# AnalogConversion_v3.net
KiCad netlist of a schematic drawn in EAGLE
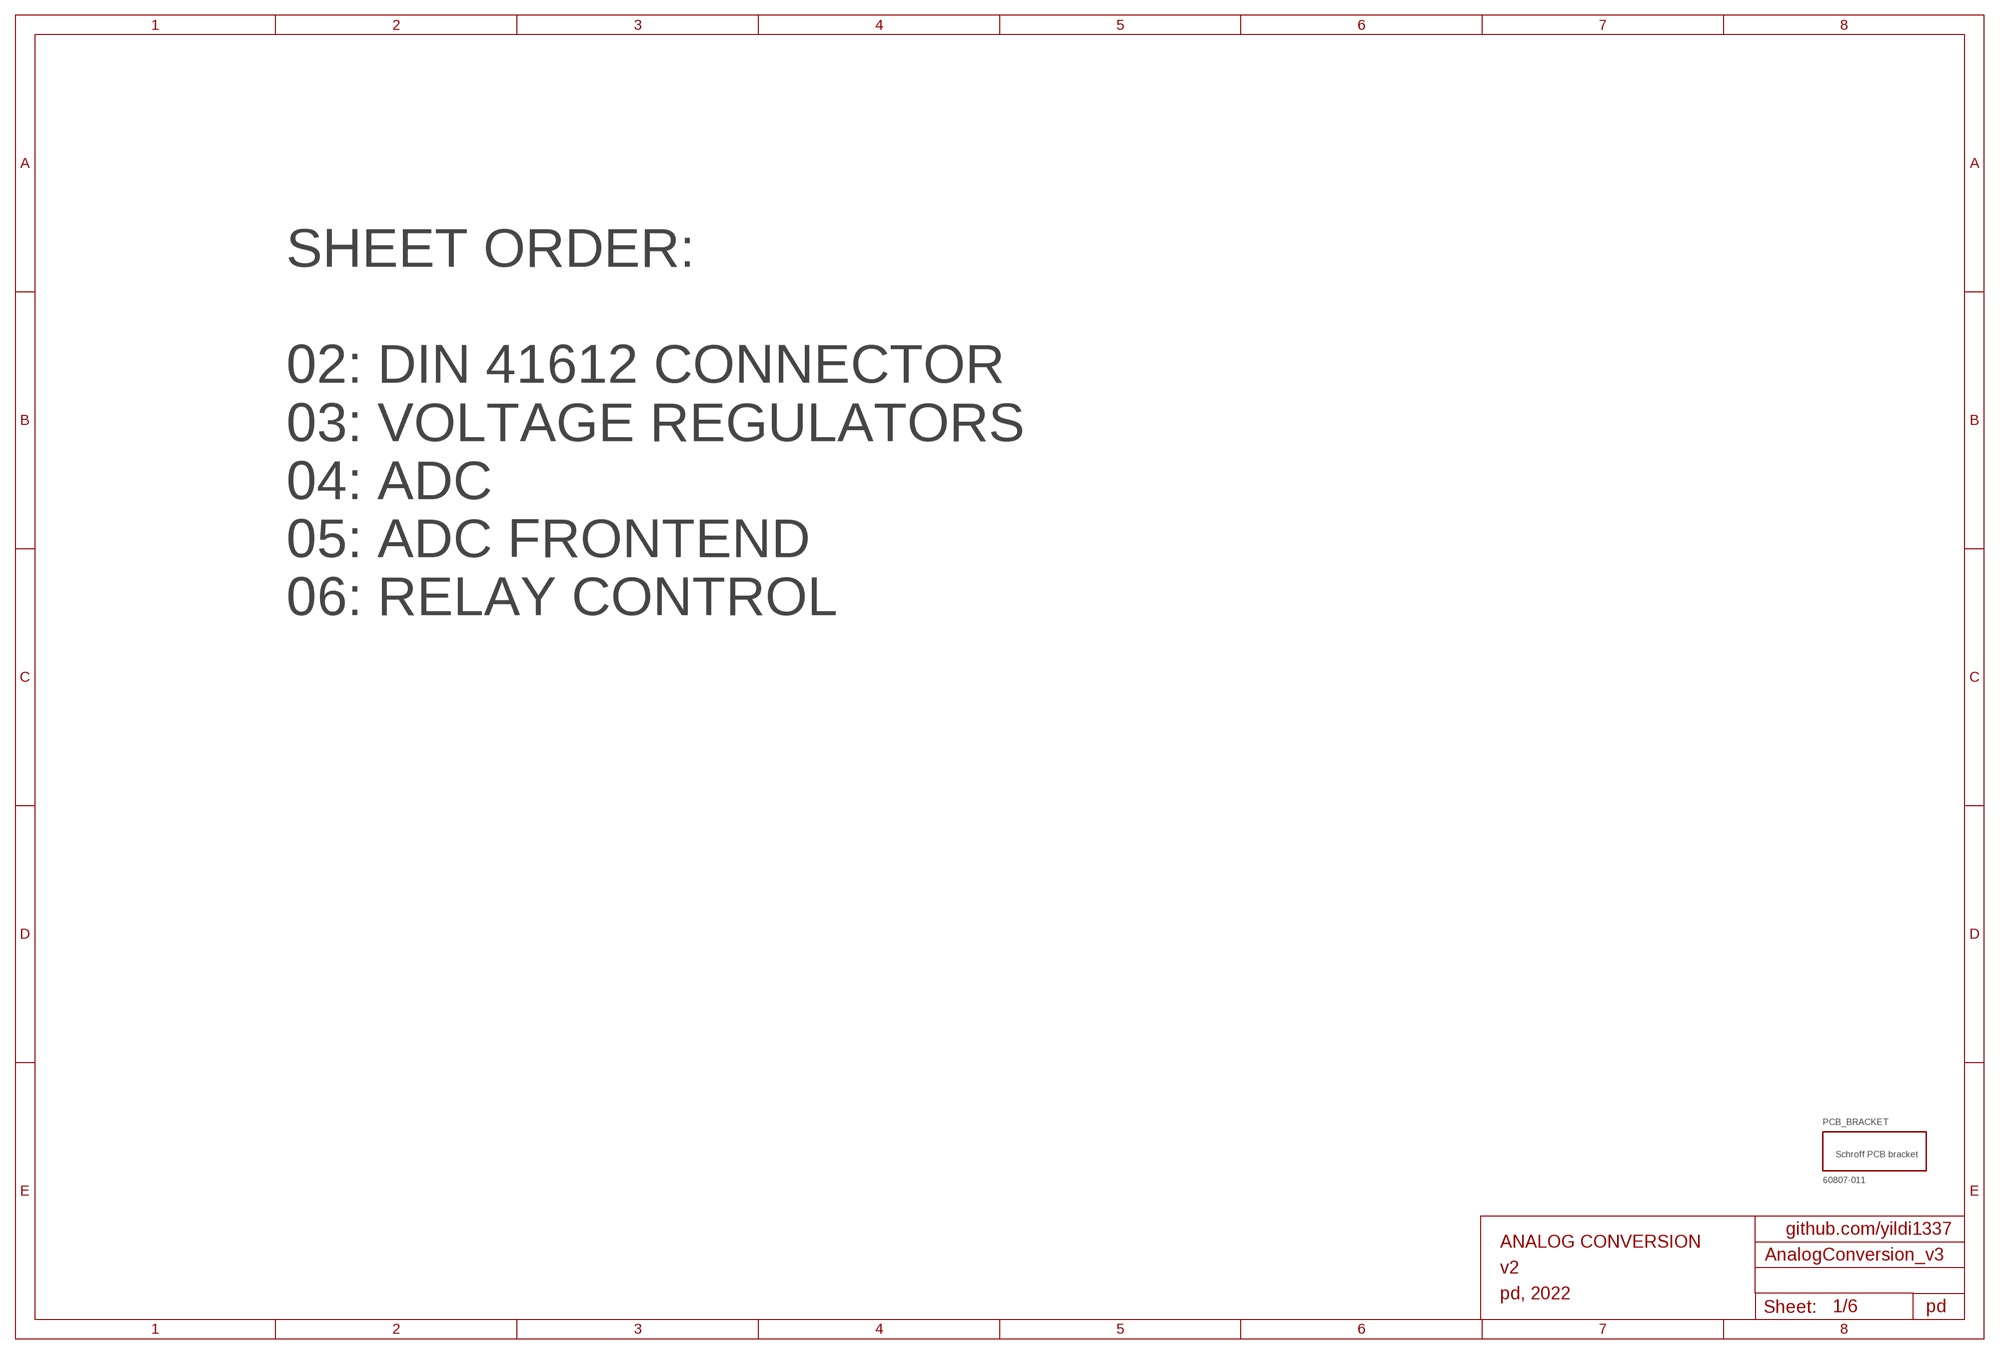
[diagram p0: schematic, sheet 1]
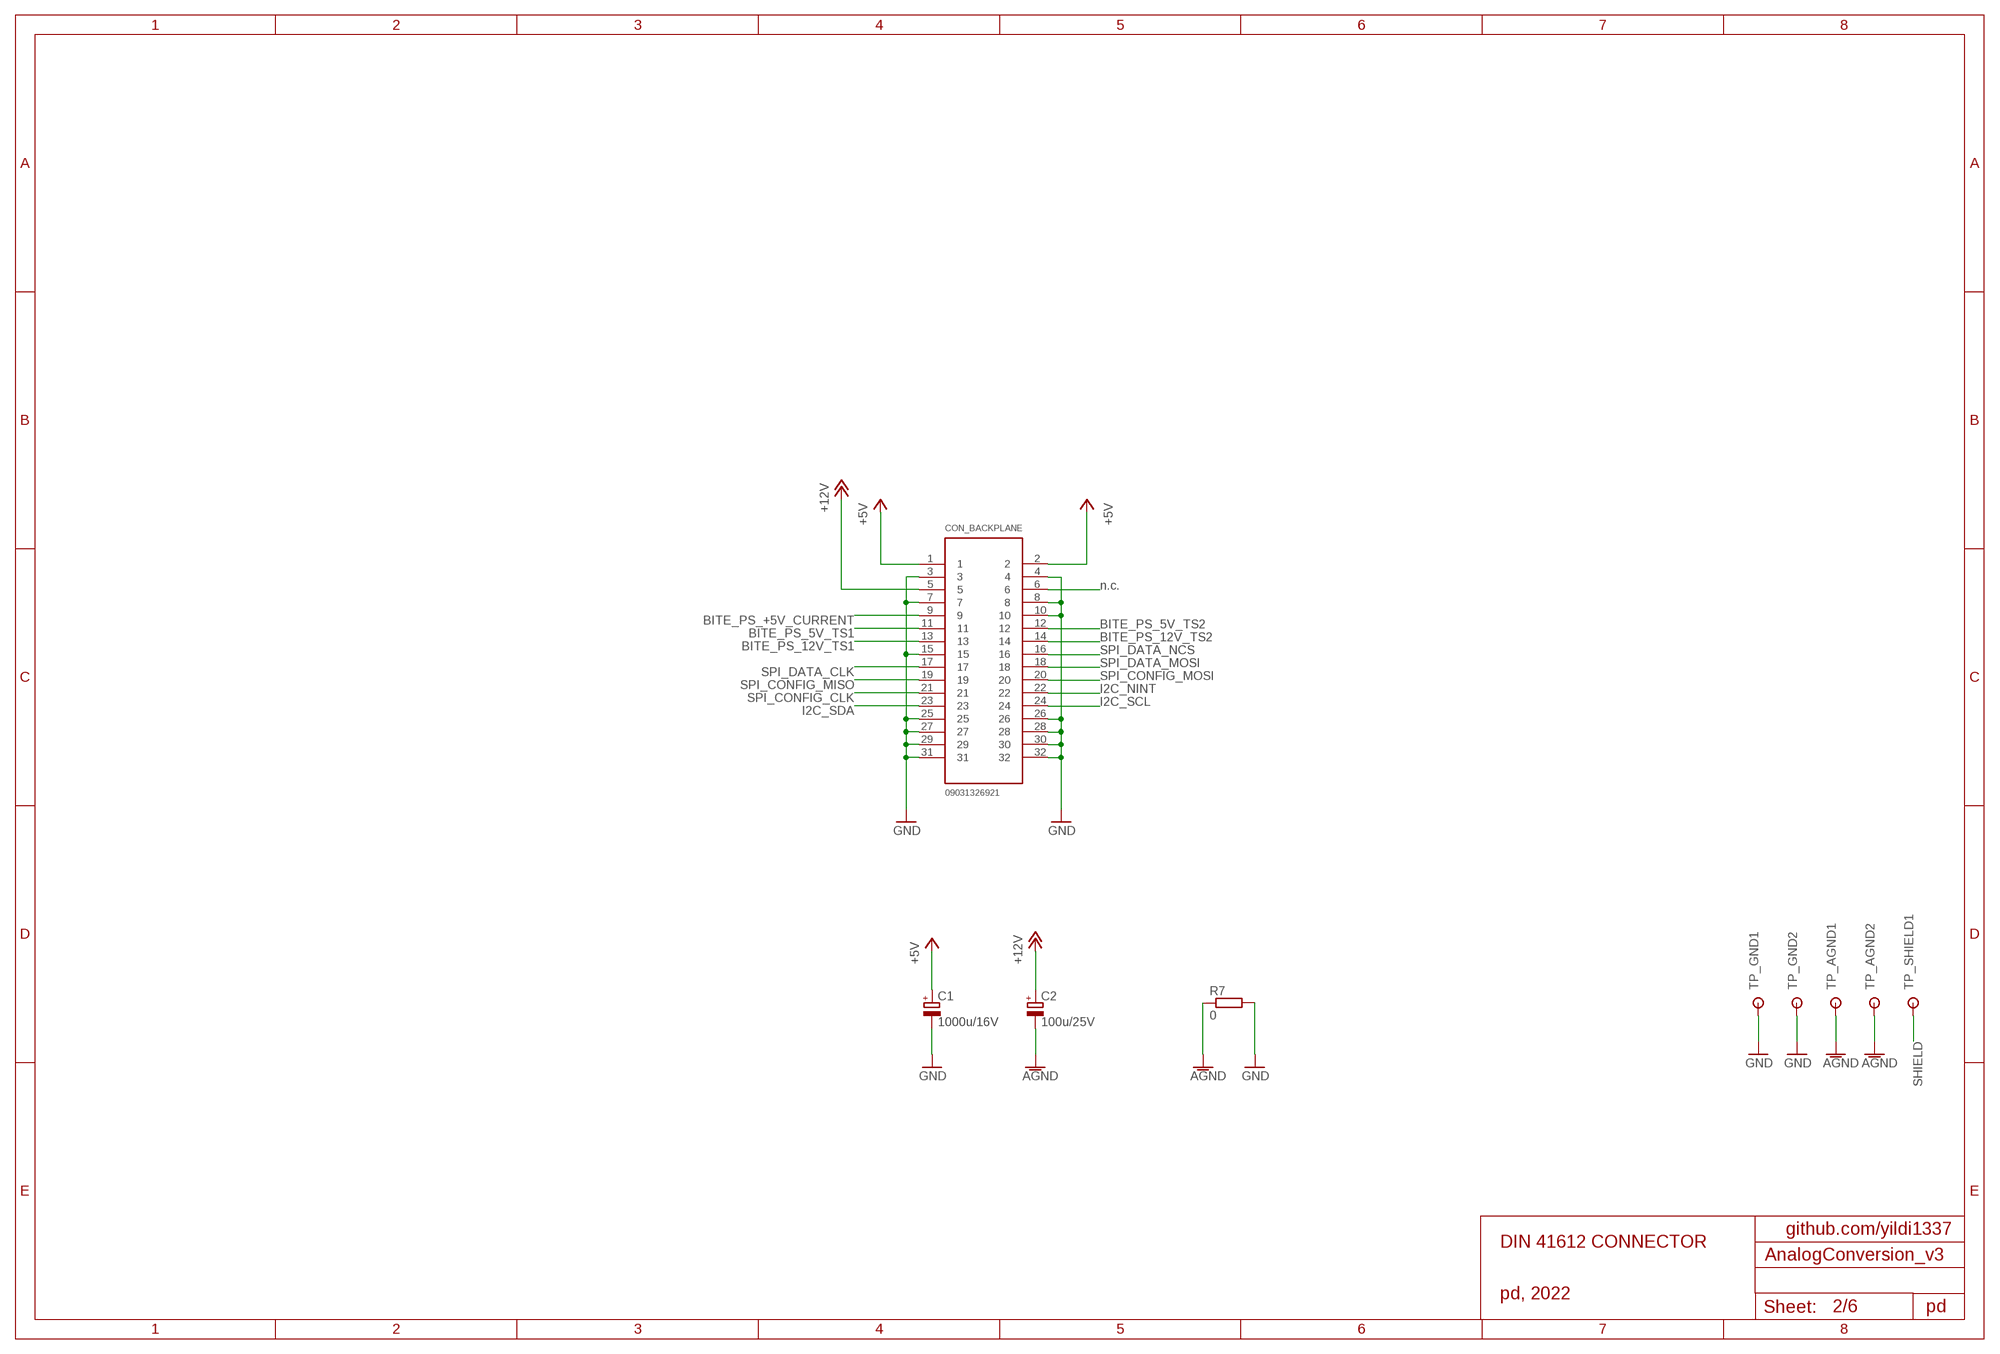
[diagram p1: schematic, sheet 2]
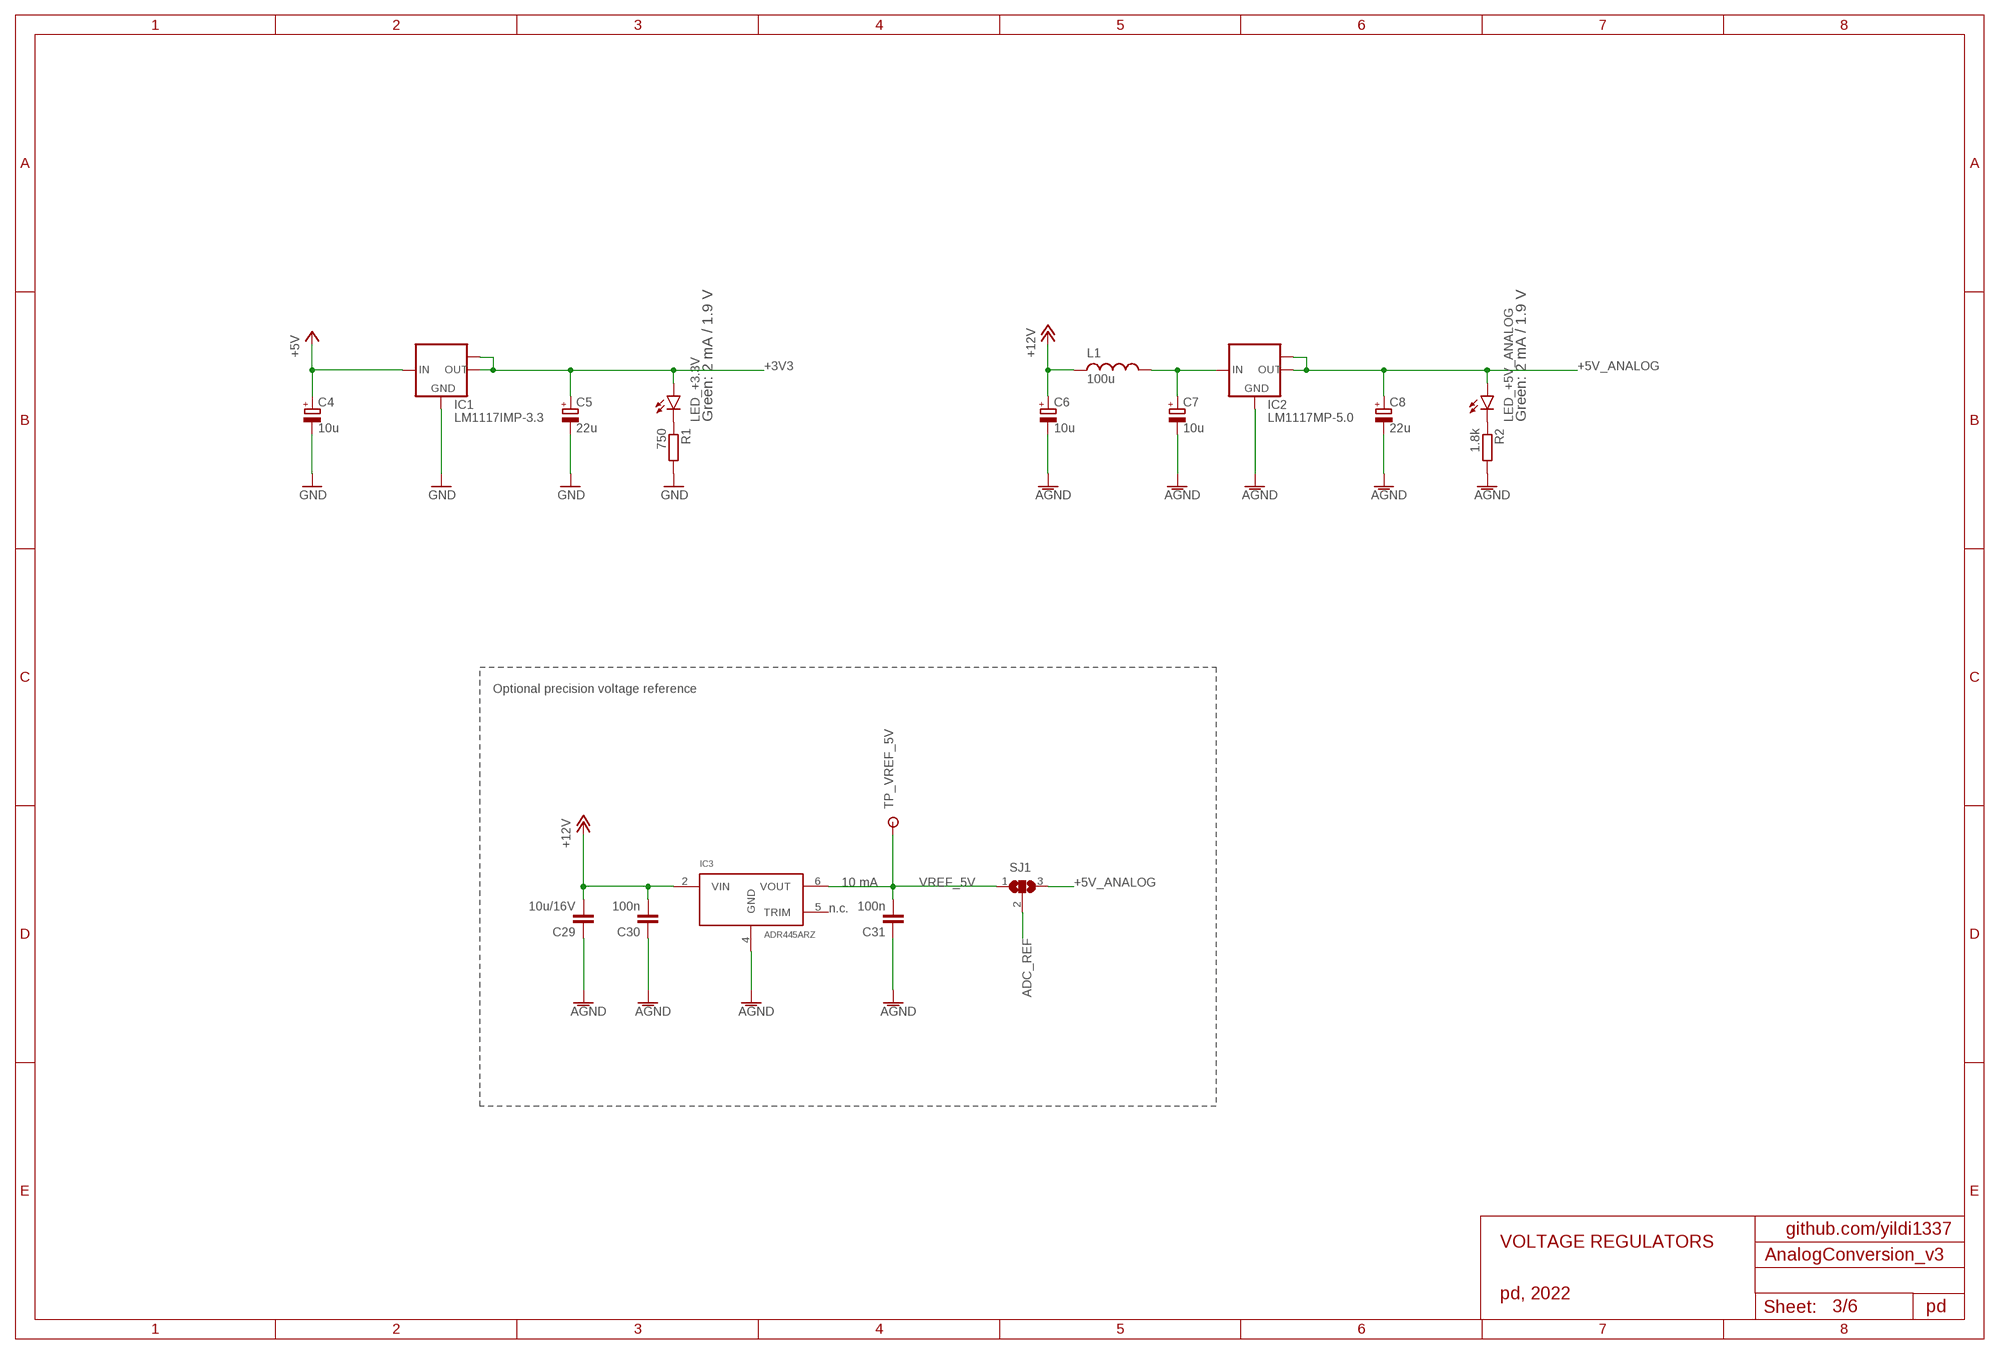
[diagram p2: schematic, sheet 3]
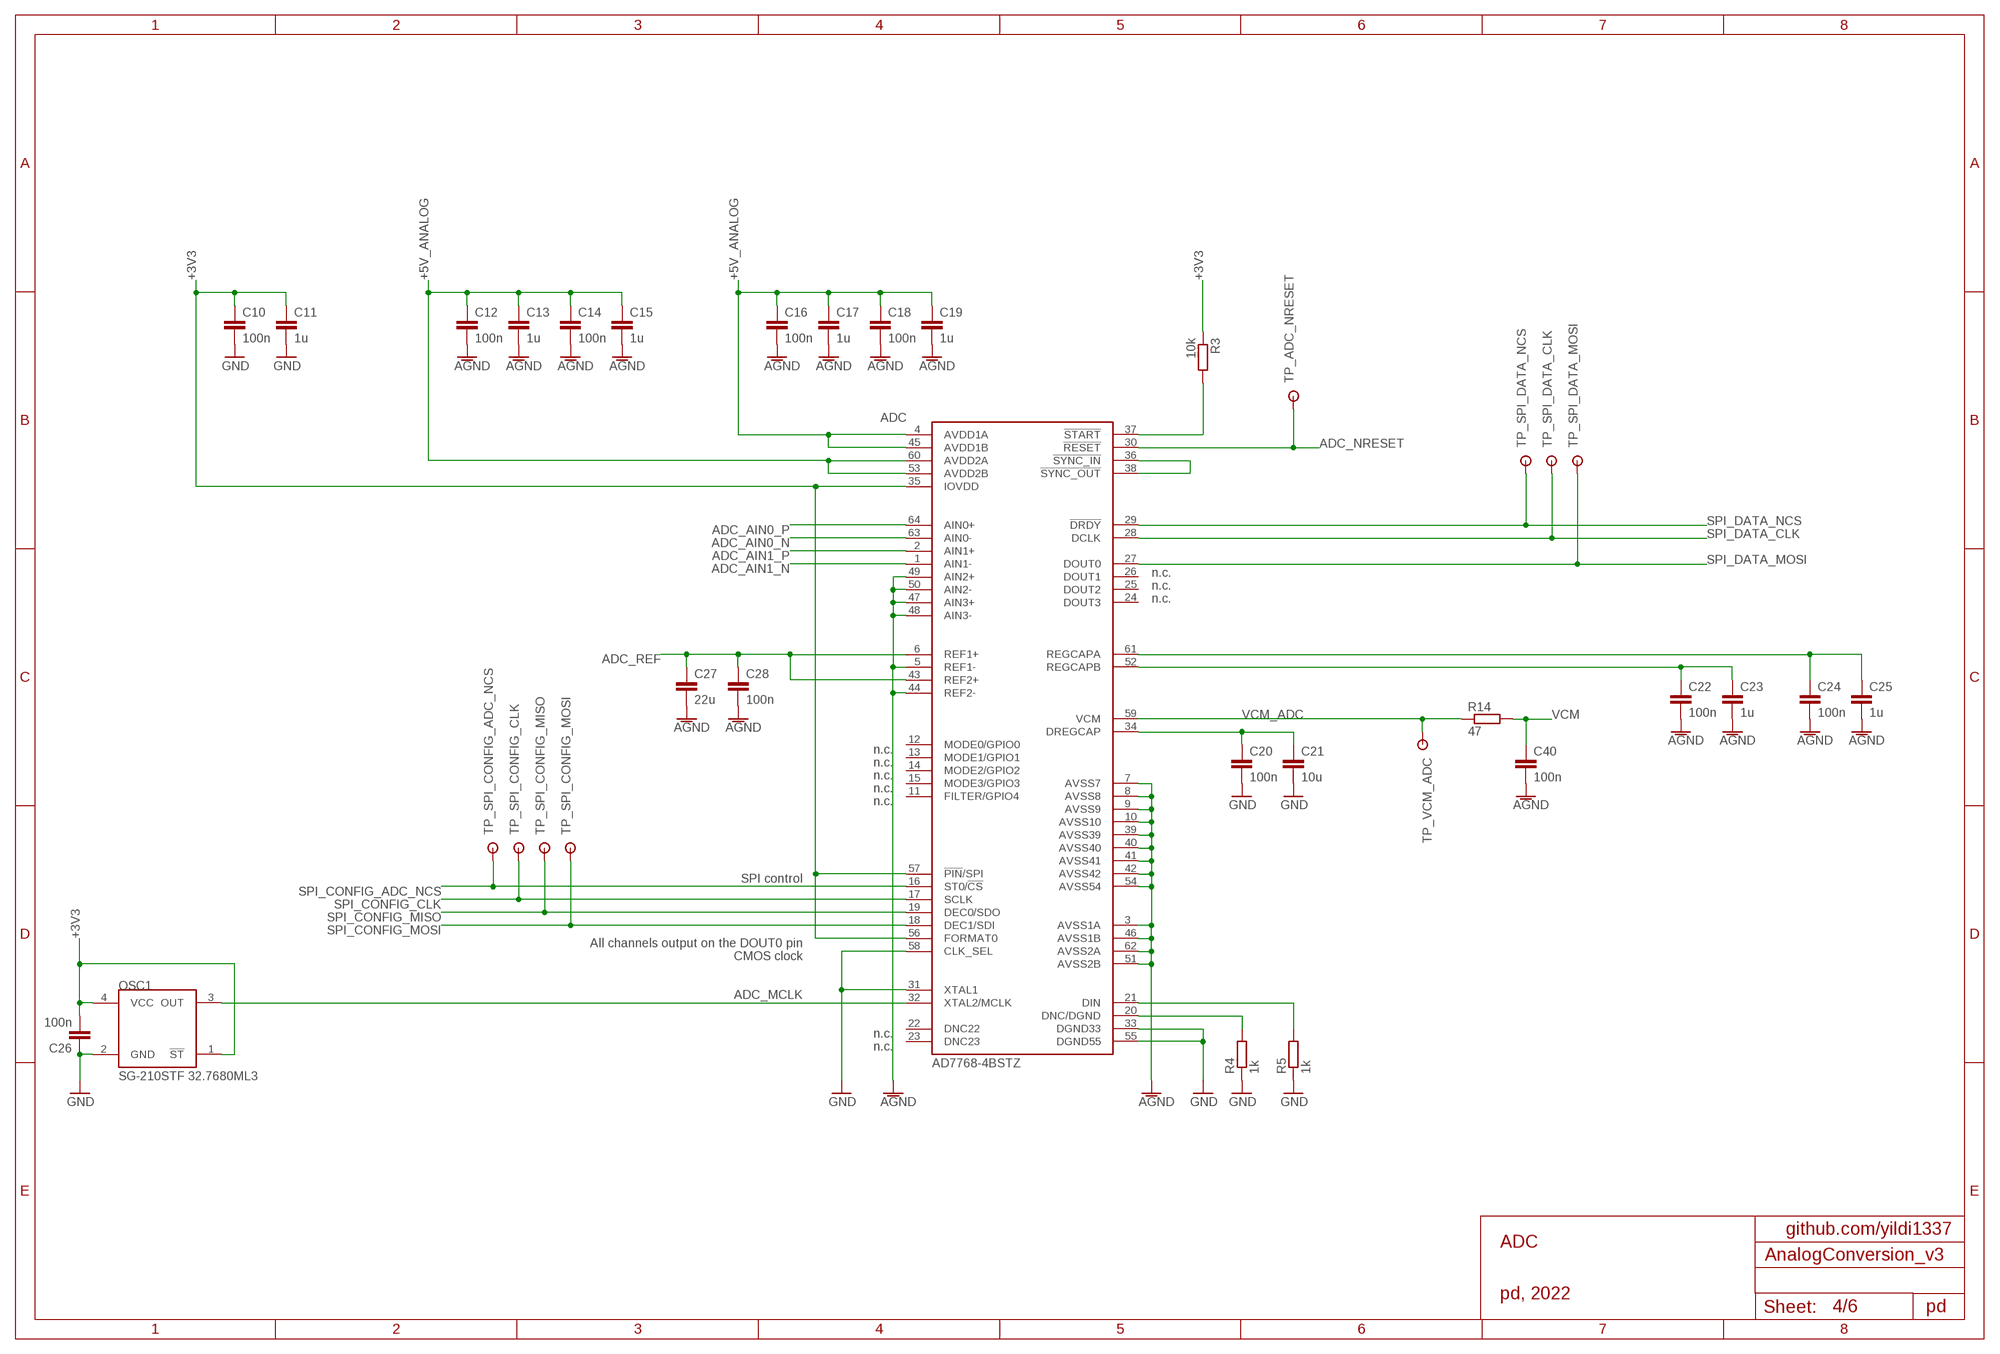
[diagram p3: schematic, sheet 4]
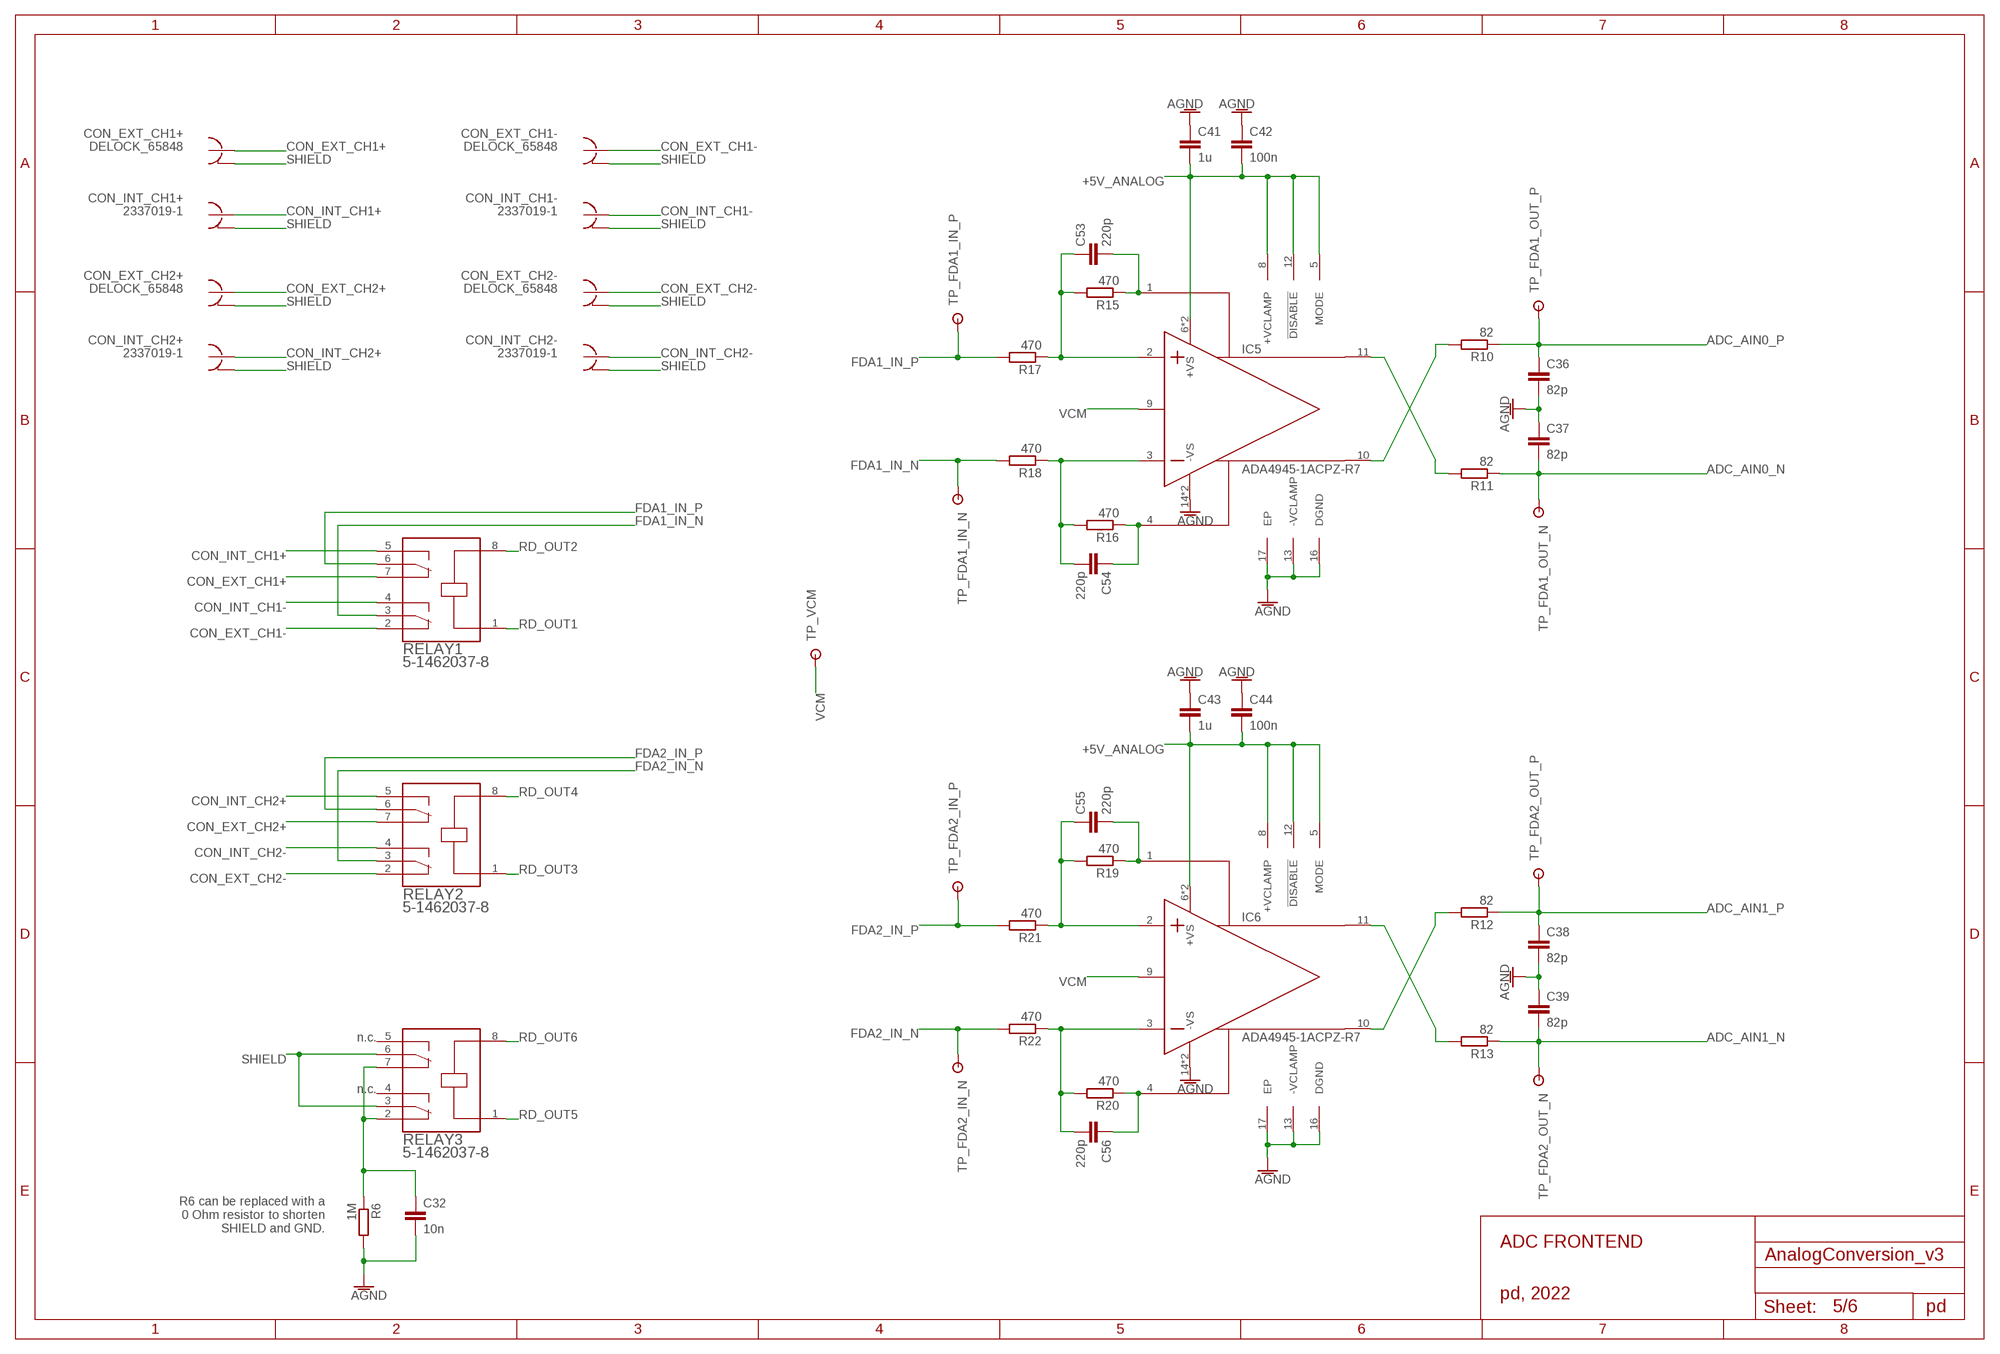
[diagram p4: schematic, sheet 5]
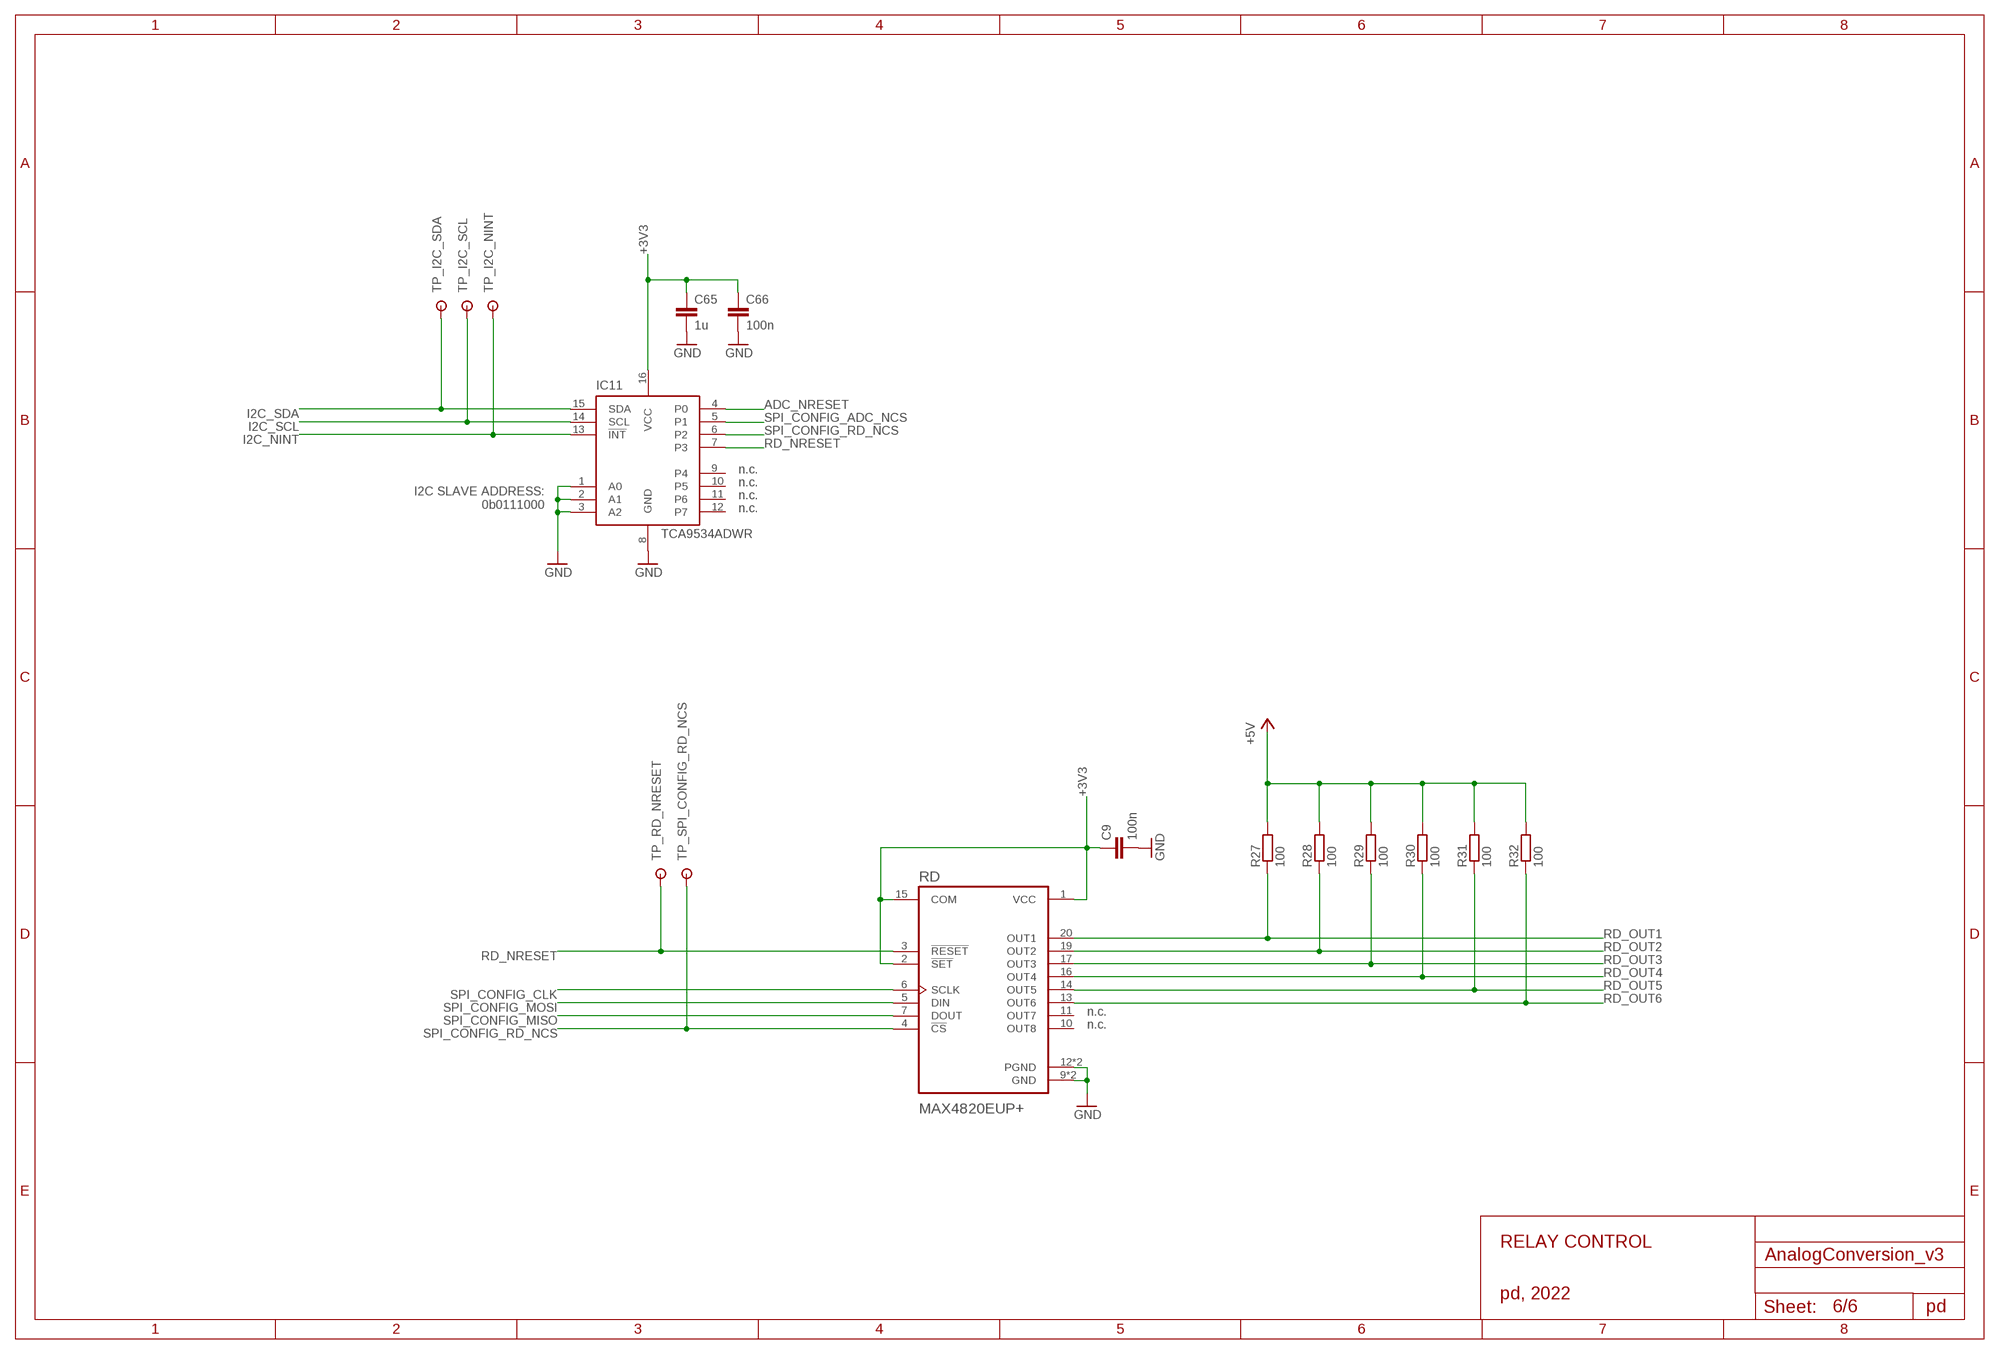
[diagram p5: schematic, sheet 6]

(export (version "E")
  (design (tool "Eeschema 10.0.6"))
  (components
    (comp (ref "ADC")
      (value "AD7768-4BSTZ")
      (footprint "eagle-import:AD7768-4BSTZ")
      (libsource (lib "eagle-import") (part "AD7768-4BSTZ"))
    )
    (comp (ref "C10")
      (value "100n")
      (footprint "eagle-import:C0603")
      (libsource (lib "eagle-import") (part "C-EUC0603"))
    )
    (comp (ref "C11")
      (value "1u")
      (footprint "eagle-import:C0603")
      (libsource (lib "eagle-import") (part "C-EUC0603"))
    )
    (comp (ref "C12")
      (value "100n")
      (footprint "eagle-import:C0603")
      (libsource (lib "eagle-import") (part "C-EUC0603"))
    )
    (comp (ref "C13")
      (value "1u")
      (footprint "eagle-import:C0603")
      (libsource (lib "eagle-import") (part "C-EUC0603"))
    )
    (comp (ref "C14")
      (value "100n")
      (footprint "eagle-import:C0603")
      (libsource (lib "eagle-import") (part "C-EUC0603"))
    )
    (comp (ref "C15")
      (value "1u")
      (footprint "eagle-import:C0603")
      (libsource (lib "eagle-import") (part "C-EUC0603"))
    )
    (comp (ref "C16")
      (value "100n")
      (footprint "eagle-import:C0603")
      (libsource (lib "eagle-import") (part "C-EUC0603"))
    )
    (comp (ref "C17")
      (value "1u")
      (footprint "eagle-import:C0603")
      (libsource (lib "eagle-import") (part "C-EUC0603"))
    )
    (comp (ref "C18")
      (value "100n")
      (footprint "eagle-import:C0603")
      (libsource (lib "eagle-import") (part "C-EUC0603"))
    )
    (comp (ref "C19")
      (value "1u")
      (footprint "eagle-import:C0603")
      (libsource (lib "eagle-import") (part "C-EUC0603"))
    )
    (comp (ref "C20")
      (value "100n")
      (footprint "eagle-import:C0603")
      (libsource (lib "eagle-import") (part "C-EUC0603"))
    )
    (comp (ref "C21")
      (value "10u")
      (footprint "eagle-import:C0603")
      (libsource (lib "eagle-import") (part "C-EUC0603"))
    )
    (comp (ref "C22")
      (value "100n")
      (footprint "eagle-import:C0603")
      (libsource (lib "eagle-import") (part "C-EUC0603"))
    )
    (comp (ref "C23")
      (value "1u")
      (footprint "eagle-import:C0603")
      (libsource (lib "eagle-import") (part "C-EUC0603"))
    )
    (comp (ref "C24")
      (value "100n")
      (footprint "eagle-import:C0603")
      (libsource (lib "eagle-import") (part "C-EUC0603"))
    )
    (comp (ref "C25")
      (value "1u")
      (footprint "eagle-import:C0603")
      (libsource (lib "eagle-import") (part "C-EUC0603"))
    )
    (comp (ref "C26")
      (value "100n")
      (footprint "eagle-import:C0603")
      (libsource (lib "eagle-import") (part "C-EUC0603"))
    )
    (comp (ref "C27")
      (value "22u")
      (footprint "eagle-import:C1206")
      (libsource (lib "eagle-import") (part "C-EUC1206"))
    )
    (comp (ref "C28")
      (value "100n")
      (footprint "eagle-import:C0603")
      (libsource (lib "eagle-import") (part "C-EUC0603"))
    )
    (comp (ref "C40")
      (value "100n")
      (footprint "eagle-import:C0603")
      (libsource (lib "eagle-import") (part "C-EUC0603"))
    )
    (comp (ref "OSC1")
      (value "SG-210STF 32.7680ML3")
      (footprint "eagle-import:SG-210STF-32.7680ML3")
      (libsource (lib "eagle-import") (part "SG-210STF-32.7680ML3"))
    )
    (comp (ref "R3")
      (value "10k")
      (footprint "eagle-import:R0603")
      (libsource (lib "eagle-import") (part "R-EU_R0603"))
    )
    (comp (ref "R4")
      (value "1k")
      (footprint "eagle-import:R0603")
      (libsource (lib "eagle-import") (part "R-EU_R0603"))
    )
    (comp (ref "R5")
      (value "1k")
      (footprint "eagle-import:R0603")
      (libsource (lib "eagle-import") (part "R-EU_R0603"))
    )
    (comp (ref "R14")
      (value "47")
      (footprint "eagle-import:R0603")
      (libsource (lib "eagle-import") (part "R-EU_R0603"))
    )
    (comp (ref "TP_ADC_NRESET")
      (value "RSPRO-1MM-TERMINAL-POST-2622034")
      (footprint "eagle-import:RSPRO-1MM-TERMINAL-POST-2622034")
      (libsource (lib "eagle-import") (part "RSPRO-1MM-TERMINAL-POST-2622034"))
    )
    (comp (ref "TP_SPI_CONFIG_ADC_NCS")
      (value "RSPRO-1MM-TERMINAL-POST-2622034")
      (footprint "eagle-import:RSPRO-1MM-TERMINAL-POST-2622034")
      (libsource (lib "eagle-import") (part "RSPRO-1MM-TERMINAL-POST-2622034"))
    )
    (comp (ref "TP_SPI_CONFIG_CLK")
      (value "RSPRO-1MM-TERMINAL-POST-2622034")
      (footprint "eagle-import:RSPRO-1MM-TERMINAL-POST-2622034")
      (libsource (lib "eagle-import") (part "RSPRO-1MM-TERMINAL-POST-2622034"))
    )
    (comp (ref "TP_SPI_CONFIG_MISO")
      (value "RSPRO-1MM-TERMINAL-POST-2622034")
      (footprint "eagle-import:RSPRO-1MM-TERMINAL-POST-2622034")
      (libsource (lib "eagle-import") (part "RSPRO-1MM-TERMINAL-POST-2622034"))
    )
    (comp (ref "TP_SPI_CONFIG_MOSI")
      (value "RSPRO-1MM-TERMINAL-POST-2622034")
      (footprint "eagle-import:RSPRO-1MM-TERMINAL-POST-2622034")
      (libsource (lib "eagle-import") (part "RSPRO-1MM-TERMINAL-POST-2622034"))
    )
    (comp (ref "TP_SPI_DATA_CLK")
      (value "RSPRO-1MM-TERMINAL-POST-2622034")
      (footprint "eagle-import:RSPRO-1MM-TERMINAL-POST-2622034")
      (libsource (lib "eagle-import") (part "RSPRO-1MM-TERMINAL-POST-2622034"))
    )
    (comp (ref "TP_SPI_DATA_MOSI")
      (value "RSPRO-1MM-TERMINAL-POST-2622034")
      (footprint "eagle-import:RSPRO-1MM-TERMINAL-POST-2622034")
      (libsource (lib "eagle-import") (part "RSPRO-1MM-TERMINAL-POST-2622034"))
    )
    (comp (ref "TP_SPI_DATA_NCS")
      (value "RSPRO-1MM-TERMINAL-POST-2622034")
      (footprint "eagle-import:RSPRO-1MM-TERMINAL-POST-2622034")
      (libsource (lib "eagle-import") (part "RSPRO-1MM-TERMINAL-POST-2622034"))
    )
    (comp (ref "TP_VCM_ADC")
      (value "RSPRO-1MM-TERMINAL-POST-2622034")
      (footprint "eagle-import:RSPRO-1MM-TERMINAL-POST-2622034")
      (libsource (lib "eagle-import") (part "RSPRO-1MM-TERMINAL-POST-2622034"))
    )
    (comp (ref "C4")
      (value "10u")
      (footprint "eagle-import:CT3216")
      (libsource (lib "eagle-import") (part "CPOL-EUCT3216"))
    )
    (comp (ref "C5")
      (value "22u")
      (footprint "eagle-import:CT6032")
      (libsource (lib "eagle-import") (part "CPOL-EUCT6032"))
    )
    (comp (ref "C6")
      (value "10u")
      (footprint "eagle-import:CT3216")
      (libsource (lib "eagle-import") (part "CPOL-EUCT3216"))
    )
    (comp (ref "C7")
      (value "10u")
      (footprint "eagle-import:CT3216")
      (libsource (lib "eagle-import") (part "CPOL-EUCT3216"))
    )
    (comp (ref "C8")
      (value "22u")
      (footprint "eagle-import:CT6032")
      (libsource (lib "eagle-import") (part "CPOL-EUCT6032"))
    )
    (comp (ref "C29")
      (value "10u/16V")
      (footprint "eagle-import:C0805")
      (libsource (lib "eagle-import") (part "C-EUC0805"))
    )
    (comp (ref "C30")
      (value "100n")
      (footprint "eagle-import:C0603")
      (libsource (lib "eagle-import") (part "C-EUC0603"))
    )
    (comp (ref "C31")
      (value "100n")
      (footprint "eagle-import:C0603")
      (libsource (lib "eagle-import") (part "C-EUC0603"))
    )
    (comp (ref "IC1")
      (value "LM1117IMP-3.3")
      (footprint "eagle-import:SOT223")
      (libsource (lib "eagle-import") (part "LM1117IMPX-3.3"))
    )
    (comp (ref "IC2")
      (value "LM1117MP-5.0")
      (footprint "eagle-import:SOT223")
      (libsource (lib "eagle-import") (part "LM1117MPX-5.0"))
    )
    (comp (ref "IC3")
      (value "ADR445ARZ")
      (footprint "eagle-import:ADR445ARZ")
      (libsource (lib "eagle-import") (part "ADR445ARZ"))
    )
    (comp (ref "L1")
      (value "100u")
      (footprint "eagle-import:VLS6045AF-101M")
      (libsource (lib "eagle-import") (part "VLS6045AF-101M"))
    )
    (comp (ref "LED_+3.3V")
      (value "LEDCHIP-LED0603")
      (footprint "eagle-import:CHIP-LED0603")
      (libsource (lib "eagle-import") (part "LEDCHIP-LED0603"))
    )
    (comp (ref "LED_+5V_ANALOG")
      (value "LEDCHIP-LED0603")
      (footprint "eagle-import:CHIP-LED0603")
      (libsource (lib "eagle-import") (part "LEDCHIP-LED0603"))
    )
    (comp (ref "R1")
      (value "750")
      (footprint "eagle-import:R0603")
      (libsource (lib "eagle-import") (part "R-EU_R0603"))
    )
    (comp (ref "R2")
      (value "1.8k")
      (footprint "eagle-import:R0603")
      (libsource (lib "eagle-import") (part "R-EU_R0603"))
    )
    (comp (ref "SJ1")
      (value "SJ2W")
      (footprint "eagle-import:SJ_2")
      (libsource (lib "eagle-import") (part "SJ2W"))
    )
    (comp (ref "TP_VREF_5V")
      (value "RSPRO-1MM-TERMINAL-POST-2622034")
      (footprint "eagle-import:RSPRO-1MM-TERMINAL-POST-2622034")
      (libsource (lib "eagle-import") (part "RSPRO-1MM-TERMINAL-POST-2622034"))
    )
    (comp (ref "PCB_BRACKET")
      (value "60807-011")
      (footprint "eagle-import:60807-011")
      (libsource (lib "eagle-import") (part "60807-011"))
    )
    (comp (ref "C32")
      (value "10n")
      (footprint "eagle-import:C0603")
      (libsource (lib "eagle-import") (part "C-EUC0603"))
    )
    (comp (ref "C36")
      (value "82p")
      (footprint "eagle-import:C0603")
      (libsource (lib "eagle-import") (part "C-EUC0603"))
    )
    (comp (ref "C37")
      (value "82p")
      (footprint "eagle-import:C0603")
      (libsource (lib "eagle-import") (part "C-EUC0603"))
    )
    (comp (ref "C38")
      (value "82p")
      (footprint "eagle-import:C0603")
      (libsource (lib "eagle-import") (part "C-EUC0603"))
    )
    (comp (ref "C39")
      (value "82p")
      (footprint "eagle-import:C0603")
      (libsource (lib "eagle-import") (part "C-EUC0603"))
    )
    (comp (ref "C41")
      (value "1u")
      (footprint "eagle-import:C0603")
      (libsource (lib "eagle-import") (part "C-EUC0603"))
    )
    (comp (ref "C42")
      (value "100n")
      (footprint "eagle-import:C0603")
      (libsource (lib "eagle-import") (part "C-EUC0603"))
    )
    (comp (ref "C43")
      (value "1u")
      (footprint "eagle-import:C0603")
      (libsource (lib "eagle-import") (part "C-EUC0603"))
    )
    (comp (ref "C44")
      (value "100n")
      (footprint "eagle-import:C0603")
      (libsource (lib "eagle-import") (part "C-EUC0603"))
    )
    (comp (ref "C53")
      (value "220p")
      (footprint "eagle-import:C0603")
      (libsource (lib "eagle-import") (part "C-EUC0603"))
    )
    (comp (ref "C54")
      (value "220p")
      (footprint "eagle-import:C0603")
      (libsource (lib "eagle-import") (part "C-EUC0603"))
    )
    (comp (ref "C55")
      (value "220p")
      (footprint "eagle-import:C0603")
      (libsource (lib "eagle-import") (part "C-EUC0603"))
    )
    (comp (ref "C56")
      (value "220p")
      (footprint "eagle-import:C0603")
      (libsource (lib "eagle-import") (part "C-EUC0603"))
    )
    (comp (ref "CON_EXT_CH1+")
      (value "DELOCK_65848")
      (footprint "eagle-import:DELOCK_65848")
      (libsource (lib "eagle-import") (part "DELOCK_65848"))
    )
    (comp (ref "CON_EXT_CH1-")
      (value "DELOCK_65848")
      (footprint "eagle-import:DELOCK_65848")
      (libsource (lib "eagle-import") (part "DELOCK_65848"))
    )
    (comp (ref "CON_EXT_CH2+")
      (value "DELOCK_65848")
      (footprint "eagle-import:DELOCK_65848")
      (libsource (lib "eagle-import") (part "DELOCK_65848"))
    )
    (comp (ref "CON_EXT_CH2-")
      (value "DELOCK_65848")
      (footprint "eagle-import:DELOCK_65848")
      (libsource (lib "eagle-import") (part "DELOCK_65848"))
    )
    (comp (ref "CON_INT_CH1+")
      (value "2337019-1")
      (footprint "eagle-import:2337019-1")
      (libsource (lib "eagle-import") (part "2337019-1"))
    )
    (comp (ref "CON_INT_CH1-")
      (value "2337019-1")
      (footprint "eagle-import:2337019-1")
      (libsource (lib "eagle-import") (part "2337019-1"))
    )
    (comp (ref "CON_INT_CH2+")
      (value "2337019-1")
      (footprint "eagle-import:2337019-1")
      (libsource (lib "eagle-import") (part "2337019-1"))
    )
    (comp (ref "CON_INT_CH2-")
      (value "2337019-1")
      (footprint "eagle-import:2337019-1")
      (libsource (lib "eagle-import") (part "2337019-1"))
    )
    (comp (ref "IC5")
      (value "ADA4945-1ACPZ-R7")
      (footprint "eagle-import:ADA4945-1ACPZ-R7")
      (libsource (lib "eagle-import") (part "ADA4945-1ACPZ-R7"))
    )
    (comp (ref "IC6")
      (value "ADA4945-1ACPZ-R7")
      (footprint "eagle-import:ADA4945-1ACPZ-R7")
      (libsource (lib "eagle-import") (part "ADA4945-1ACPZ-R7"))
    )
    (comp (ref "R6")
      (value "1M")
      (footprint "eagle-import:R0603")
      (libsource (lib "eagle-import") (part "R-EU_R0603"))
    )
    (comp (ref "R10")
      (value "82")
      (footprint "eagle-import:R0603")
      (libsource (lib "eagle-import") (part "R-EU_R0603"))
    )
    (comp (ref "R11")
      (value "82")
      (footprint "eagle-import:R0603")
      (libsource (lib "eagle-import") (part "R-EU_R0603"))
    )
    (comp (ref "R12")
      (value "82")
      (footprint "eagle-import:R0603")
      (libsource (lib "eagle-import") (part "R-EU_R0603"))
    )
    (comp (ref "R13")
      (value "82")
      (footprint "eagle-import:R0603")
      (libsource (lib "eagle-import") (part "R-EU_R0603"))
    )
    (comp (ref "R15")
      (value "470")
      (footprint "eagle-import:R0603")
      (libsource (lib "eagle-import") (part "R-EU_R0603"))
    )
    (comp (ref "R16")
      (value "470")
      (footprint "eagle-import:R0603")
      (libsource (lib "eagle-import") (part "R-EU_R0603"))
    )
    (comp (ref "R17")
      (value "470")
      (footprint "eagle-import:R0603")
      (libsource (lib "eagle-import") (part "R-EU_R0603"))
    )
    (comp (ref "R18")
      (value "470")
      (footprint "eagle-import:R0603")
      (libsource (lib "eagle-import") (part "R-EU_R0603"))
    )
    (comp (ref "R19")
      (value "470")
      (footprint "eagle-import:R0603")
      (libsource (lib "eagle-import") (part "R-EU_R0603"))
    )
    (comp (ref "R20")
      (value "470")
      (footprint "eagle-import:R0603")
      (libsource (lib "eagle-import") (part "R-EU_R0603"))
    )
    (comp (ref "R21")
      (value "470")
      (footprint "eagle-import:R0603")
      (libsource (lib "eagle-import") (part "R-EU_R0603"))
    )
    (comp (ref "R22")
      (value "470")
      (footprint "eagle-import:R0603")
      (libsource (lib "eagle-import") (part "R-EU_R0603"))
    )
    (comp (ref "RELAY1")
      (value "5-1462037-8")
      (footprint "eagle-import:5-1462037-8")
      (libsource (lib "eagle-import") (part "5-1462037-8"))
    )
    (comp (ref "RELAY2")
      (value "5-1462037-8")
      (footprint "eagle-import:5-1462037-8")
      (libsource (lib "eagle-import") (part "5-1462037-8"))
    )
    (comp (ref "RELAY3")
      (value "5-1462037-8")
      (footprint "eagle-import:5-1462037-8")
      (libsource (lib "eagle-import") (part "5-1462037-8"))
    )
    (comp (ref "TP_FDA1_IN_N")
      (value "RSPRO-1MM-TERMINAL-POST-2622034")
      (footprint "eagle-import:RSPRO-1MM-TERMINAL-POST-2622034")
      (libsource (lib "eagle-import") (part "RSPRO-1MM-TERMINAL-POST-2622034"))
    )
    (comp (ref "TP_FDA1_IN_P")
      (value "RSPRO-1MM-TERMINAL-POST-2622034")
      (footprint "eagle-import:RSPRO-1MM-TERMINAL-POST-2622034")
      (libsource (lib "eagle-import") (part "RSPRO-1MM-TERMINAL-POST-2622034"))
    )
    (comp (ref "TP_FDA1_OUT_N")
      (value "RSPRO-1MM-TERMINAL-POST-2622034")
      (footprint "eagle-import:RSPRO-1MM-TERMINAL-POST-2622034")
      (libsource (lib "eagle-import") (part "RSPRO-1MM-TERMINAL-POST-2622034"))
    )
    (comp (ref "TP_FDA1_OUT_P")
      (value "RSPRO-1MM-TERMINAL-POST-2622034")
      (footprint "eagle-import:RSPRO-1MM-TERMINAL-POST-2622034")
      (libsource (lib "eagle-import") (part "RSPRO-1MM-TERMINAL-POST-2622034"))
    )
    (comp (ref "TP_FDA2_IN_N")
      (value "RSPRO-1MM-TERMINAL-POST-2622034")
      (footprint "eagle-import:RSPRO-1MM-TERMINAL-POST-2622034")
      (libsource (lib "eagle-import") (part "RSPRO-1MM-TERMINAL-POST-2622034"))
    )
    (comp (ref "TP_FDA2_IN_P")
      (value "RSPRO-1MM-TERMINAL-POST-2622034")
      (footprint "eagle-import:RSPRO-1MM-TERMINAL-POST-2622034")
      (libsource (lib "eagle-import") (part "RSPRO-1MM-TERMINAL-POST-2622034"))
    )
    (comp (ref "TP_FDA2_OUT_N")
      (value "RSPRO-1MM-TERMINAL-POST-2622034")
      (footprint "eagle-import:RSPRO-1MM-TERMINAL-POST-2622034")
      (libsource (lib "eagle-import") (part "RSPRO-1MM-TERMINAL-POST-2622034"))
    )
    (comp (ref "TP_FDA2_OUT_P")
      (value "RSPRO-1MM-TERMINAL-POST-2622034")
      (footprint "eagle-import:RSPRO-1MM-TERMINAL-POST-2622034")
      (libsource (lib "eagle-import") (part "RSPRO-1MM-TERMINAL-POST-2622034"))
    )
    (comp (ref "TP_VCM")
      (value "RSPRO-1MM-TERMINAL-POST-2622034")
      (footprint "eagle-import:RSPRO-1MM-TERMINAL-POST-2622034")
      (libsource (lib "eagle-import") (part "RSPRO-1MM-TERMINAL-POST-2622034"))
    )
    (comp (ref "C1")
      (value "1000u/16V")
      (footprint "eagle-import:153CLV-1010")
      (libsource (lib "eagle-import") (part "rcl_18640681_CPOL-EU153CLV-1010"))
    )
    (comp (ref "C2")
      (value "100u/25V")
      (footprint "eagle-import:153CLV-0810")
      (libsource (lib "eagle-import") (part "rcl_18640681_CPOL-EU153CLV-0810"))
    )
    (comp (ref "CON_BACKPLANE")
      (value "09031326921")
      (footprint "eagle-import:09031326921")
      (libsource (lib "eagle-import") (part "09031326921"))
    )
    (comp (ref "R7")
      (value "0")
      (footprint "eagle-import:R0603")
      (libsource (lib "eagle-import") (part "R-EU_R0603"))
    )
    (comp (ref "TP_AGND1")
      (value "RSPRO-1MM-TERMINAL-POST-2622034")
      (footprint "eagle-import:RSPRO-1MM-TERMINAL-POST-2622034")
      (libsource (lib "eagle-import") (part "RSPRO-1MM-TERMINAL-POST-2622034"))
    )
    (comp (ref "TP_AGND2")
      (value "RSPRO-1MM-TERMINAL-POST-2622034")
      (footprint "eagle-import:RSPRO-1MM-TERMINAL-POST-2622034")
      (libsource (lib "eagle-import") (part "RSPRO-1MM-TERMINAL-POST-2622034"))
    )
    (comp (ref "TP_GND1")
      (value "RSPRO-1MM-TERMINAL-POST-2622034")
      (footprint "eagle-import:RSPRO-1MM-TERMINAL-POST-2622034")
      (libsource (lib "eagle-import") (part "RSPRO-1MM-TERMINAL-POST-2622034"))
    )
    (comp (ref "TP_GND2")
      (value "RSPRO-1MM-TERMINAL-POST-2622034")
      (footprint "eagle-import:RSPRO-1MM-TERMINAL-POST-2622034")
      (libsource (lib "eagle-import") (part "RSPRO-1MM-TERMINAL-POST-2622034"))
    )
    (comp (ref "TP_SHIELD1")
      (value "RSPRO-1MM-TERMINAL-POST-2622034")
      (footprint "eagle-import:RSPRO-1MM-TERMINAL-POST-2622034")
      (libsource (lib "eagle-import") (part "RSPRO-1MM-TERMINAL-POST-2622034"))
    )
    (comp (ref "C9")
      (value "100n")
      (footprint "eagle-import:C0603")
      (libsource (lib "eagle-import") (part "C-EUC0603"))
    )
    (comp (ref "C65")
      (value "1u")
      (footprint "eagle-import:C0603")
      (libsource (lib "eagle-import") (part "C-EUC0603"))
    )
    (comp (ref "C66")
      (value "100n")
      (footprint "eagle-import:C0603")
      (libsource (lib "eagle-import") (part "C-EUC0603"))
    )
    (comp (ref "IC11")
      (value "TCA9534ADWR")
      (footprint "eagle-import:TCA9534ADWR")
      (libsource (lib "eagle-import") (part "TCA9534ADWR"))
    )
    (comp (ref "R27")
      (value "100")
      (footprint "eagle-import:R0603")
      (libsource (lib "eagle-import") (part "R-EU_R0603"))
    )
    (comp (ref "R28")
      (value "100")
      (footprint "eagle-import:R0603")
      (libsource (lib "eagle-import") (part "R-EU_R0603"))
    )
    (comp (ref "R29")
      (value "100")
      (footprint "eagle-import:R0603")
      (libsource (lib "eagle-import") (part "R-EU_R0603"))
    )
    (comp (ref "R30")
      (value "100")
      (footprint "eagle-import:R0603")
      (libsource (lib "eagle-import") (part "R-EU_R0603"))
    )
    (comp (ref "R31")
      (value "100")
      (footprint "eagle-import:R0603")
      (libsource (lib "eagle-import") (part "R-EU_R0603"))
    )
    (comp (ref "R32")
      (value "100")
      (footprint "eagle-import:R0603")
      (libsource (lib "eagle-import") (part "R-EU_R0603"))
    )
    (comp (ref "RD")
      (value "MAX4820EUP+")
      (footprint "eagle-import:MAX4820EUP+")
      (libsource (lib "eagle-import") (part "MAX4820EUP+"))
    )
    (comp (ref "TP_I2C_NINT")
      (value "RSPRO-1MM-TERMINAL-POST-2622034")
      (footprint "eagle-import:RSPRO-1MM-TERMINAL-POST-2622034")
      (libsource (lib "eagle-import") (part "RSPRO-1MM-TERMINAL-POST-2622034"))
    )
    (comp (ref "TP_I2C_SCL")
      (value "RSPRO-1MM-TERMINAL-POST-2622034")
      (footprint "eagle-import:RSPRO-1MM-TERMINAL-POST-2622034")
      (libsource (lib "eagle-import") (part "RSPRO-1MM-TERMINAL-POST-2622034"))
    )
    (comp (ref "TP_I2C_SDA")
      (value "RSPRO-1MM-TERMINAL-POST-2622034")
      (footprint "eagle-import:RSPRO-1MM-TERMINAL-POST-2622034")
      (libsource (lib "eagle-import") (part "RSPRO-1MM-TERMINAL-POST-2622034"))
    )
    (comp (ref "TP_RD_NRESET")
      (value "RSPRO-1MM-TERMINAL-POST-2622034")
      (footprint "eagle-import:RSPRO-1MM-TERMINAL-POST-2622034")
      (libsource (lib "eagle-import") (part "RSPRO-1MM-TERMINAL-POST-2622034"))
    )
    (comp (ref "TP_SPI_CONFIG_RD_NCS")
      (value "RSPRO-1MM-TERMINAL-POST-2622034")
      (footprint "eagle-import:RSPRO-1MM-TERMINAL-POST-2622034")
      (libsource (lib "eagle-import") (part "RSPRO-1MM-TERMINAL-POST-2622034"))
    )
  )
  (nets
    (net (code "1") (name "+3V3") (class "Default")
      (node (ref "ADC") (pin "35") (pinfunction "IOVDD_35") (pintype "power_in"))
      (node (ref "ADC") (pin "56") (pinfunction "FORMAT0_56") (pintype "input"))
      (node (ref "ADC") (pin "57") (pinfunction "~{PIN}/SPI_57") (pintype "input"))
      (node (ref "C10") (pin "1") (pinfunction "1_1") (pintype "passive"))
      (node (ref "C11") (pin "1") (pinfunction "1_1") (pintype "passive"))
      (node (ref "C26") (pin "2") (pinfunction "2_2") (pintype "passive"))
      (node (ref "C5") (pin "+") (pinfunction "+_+") (pintype "passive"))
      (node (ref "C65") (pin "1") (pinfunction "1_1") (pintype "passive"))
      (node (ref "C66") (pin "1") (pinfunction "1_1") (pintype "passive"))
      (node (ref "C9") (pin "1") (pinfunction "1_1") (pintype "passive"))
      (node (ref "IC1") (pin "2") (pinfunction "OUT_2") (pintype "passive"))
      (node (ref "IC1") (pin "TAB") (pinfunction "OUT1_TAB") (pintype "passive"))
      (node (ref "IC11") (pin "16") (pinfunction "VCC_16") (pintype "power_in"))
      (node (ref "LED_+3.3V") (pin "A") (pinfunction "A_A") (pintype "passive"))
      (node (ref "OSC1") (pin "1") (pinfunction "~{ST}_1") (pintype "bidirectional"))
      (node (ref "OSC1") (pin "4") (pinfunction "VCC_4") (pintype "bidirectional"))
      (node (ref "R3") (pin "1") (pinfunction "1_1") (pintype "passive"))
      (node (ref "RD") (pin "1") (pinfunction "VCC_1") (pintype "power_in"))
      (node (ref "RD") (pin "15") (pinfunction "COM_15") (pintype "input"))
      (node (ref "RD") (pin "2") (pinfunction "~{SET}_2") (pintype "input"))
    )
    (net (code "2") (name "+5V") (class "Default")
      (node (ref "C1") (pin "+") (pinfunction "+_+") (pintype "passive"))
      (node (ref "C4") (pin "+") (pinfunction "+_+") (pintype "passive"))
      (node (ref "CON_BACKPLANE") (pin "1") (pinfunction "1_1") (pintype "bidirectional"))
      (node (ref "CON_BACKPLANE") (pin "2") (pinfunction "2_2") (pintype "bidirectional"))
      (node (ref "IC1") (pin "3") (pinfunction "IN_3") (pintype "input"))
      (node (ref "R27") (pin "2") (pinfunction "2_2") (pintype "passive"))
      (node (ref "R28") (pin "2") (pinfunction "2_2") (pintype "passive"))
      (node (ref "R29") (pin "2") (pinfunction "2_2") (pintype "passive"))
      (node (ref "R30") (pin "2") (pinfunction "2_2") (pintype "passive"))
      (node (ref "R31") (pin "2") (pinfunction "2_2") (pintype "passive"))
      (node (ref "R32") (pin "2") (pinfunction "2_2") (pintype "passive"))
    )
    (net (code "3") (name "+5V_ANALOG") (class "Default")
      (node (ref "ADC") (pin "4") (pinfunction "AVDD1A_4") (pintype "power_in"))
      (node (ref "ADC") (pin "45") (pinfunction "AVDD1B_45") (pintype "passive"))
      (node (ref "ADC") (pin "53") (pinfunction "AVDD2B_53") (pintype "power_in"))
      (node (ref "ADC") (pin "60") (pinfunction "AVDD2A_60") (pintype "power_in"))
      (node (ref "C12") (pin "1") (pinfunction "1_1") (pintype "passive"))
      (node (ref "C13") (pin "1") (pinfunction "1_1") (pintype "passive"))
      (node (ref "C14") (pin "1") (pinfunction "1_1") (pintype "passive"))
      (node (ref "C15") (pin "1") (pinfunction "1_1") (pintype "passive"))
      (node (ref "C16") (pin "1") (pinfunction "1_1") (pintype "passive"))
      (node (ref "C17") (pin "1") (pinfunction "1_1") (pintype "passive"))
      (node (ref "C18") (pin "1") (pinfunction "1_1") (pintype "passive"))
      (node (ref "C19") (pin "1") (pinfunction "1_1") (pintype "passive"))
      (node (ref "C41") (pin "2") (pinfunction "2_2") (pintype "passive"))
      (node (ref "C42") (pin "2") (pinfunction "2_2") (pintype "passive"))
      (node (ref "C43") (pin "2") (pinfunction "2_2") (pintype "passive"))
      (node (ref "C44") (pin "2") (pinfunction "2_2") (pintype "passive"))
      (node (ref "C8") (pin "+") (pinfunction "+_+") (pintype "passive"))
      (node (ref "IC2") (pin "2") (pinfunction "OUT_2") (pintype "passive"))
      (node (ref "IC2") (pin "TAB") (pinfunction "OUT1_TAB") (pintype "passive"))
      (node (ref "IC5") (pin "12") (pinfunction "~{DISABLE}_12") (pintype "input"))
      (node (ref "IC5") (pin "5") (pinfunction "MODE_5") (pintype "input"))
      (node (ref "IC5") (pin "6") (pinfunction "+VS_6") (pintype "power_in"))
      (node (ref "IC5") (pin "7") (pinfunction "+VS_7") (pintype "power_in"))
      (node (ref "IC5") (pin "8") (pinfunction "+VCLAMP_8") (pintype "power_in"))
      (node (ref "IC6") (pin "12") (pinfunction "~{DISABLE}_12") (pintype "input"))
      (node (ref "IC6") (pin "5") (pinfunction "MODE_5") (pintype "input"))
      (node (ref "IC6") (pin "6") (pinfunction "+VS_6") (pintype "power_in"))
      (node (ref "IC6") (pin "7") (pinfunction "+VS_7") (pintype "power_in"))
      (node (ref "IC6") (pin "8") (pinfunction "+VCLAMP_8") (pintype "power_in"))
      (node (ref "LED_+5V_ANALOG") (pin "A") (pinfunction "A_A") (pintype "passive"))
      (node (ref "SJ1") (pin "3") (pinfunction "3_3") (pintype "passive"))
    )
    (net (code "4") (name "+12V") (class "Default")
      (node (ref "C2") (pin "+") (pinfunction "+_+") (pintype "passive"))
      (node (ref "C29") (pin "2") (pinfunction "2_2") (pintype "passive"))
      (node (ref "C30") (pin "2") (pinfunction "2_2") (pintype "passive"))
      (node (ref "C6") (pin "+") (pinfunction "+_+") (pintype "passive"))
      (node (ref "CON_BACKPLANE") (pin "5") (pinfunction "5_5") (pintype "bidirectional"))
      (node (ref "IC3") (pin "2") (pinfunction "VIN_2") (pintype "bidirectional"))
      (node (ref "L1") (pin "1") (pinfunction "1_1") (pintype "passive"))
    )
    (net (code "5") (name "ADC_AIN0_N") (class "Default")
      (node (ref "ADC") (pin "63") (pinfunction "AIN0-_63") (pintype "input"))
      (node (ref "C37") (pin "2") (pinfunction "2_2") (pintype "passive"))
      (node (ref "R11") (pin "1") (pinfunction "1_1") (pintype "passive"))
      (node (ref "TP_FDA1_OUT_N") (pin "P$1") (pinfunction "P$1_P$1") (pintype "bidirectional"))
    )
    (net (code "6") (name "ADC_AIN0_P") (class "Default")
      (node (ref "ADC") (pin "64") (pinfunction "AIN0+_64") (pintype "input"))
      (node (ref "C36") (pin "1") (pinfunction "1_1") (pintype "passive"))
      (node (ref "R10") (pin "1") (pinfunction "1_1") (pintype "passive"))
      (node (ref "TP_FDA1_OUT_P") (pin "P$1") (pinfunction "P$1_P$1") (pintype "bidirectional"))
    )
    (net (code "7") (name "ADC_AIN1_N") (class "Default")
      (node (ref "ADC") (pin "1") (pinfunction "AIN1-_1") (pintype "input"))
      (node (ref "C39") (pin "2") (pinfunction "2_2") (pintype "passive"))
      (node (ref "R13") (pin "1") (pinfunction "1_1") (pintype "passive"))
      (node (ref "TP_FDA2_OUT_N") (pin "P$1") (pinfunction "P$1_P$1") (pintype "bidirectional"))
    )
    (net (code "8") (name "ADC_AIN1_P") (class "Default")
      (node (ref "ADC") (pin "2") (pinfunction "AIN1+_2") (pintype "input"))
      (node (ref "C38") (pin "1") (pinfunction "1_1") (pintype "passive"))
      (node (ref "R12") (pin "1") (pinfunction "1_1") (pintype "passive"))
      (node (ref "TP_FDA2_OUT_P") (pin "P$1") (pinfunction "P$1_P$1") (pintype "bidirectional"))
    )
    (net (code "9") (name "ADC_MCLK") (class "Default")
      (node (ref "ADC") (pin "32") (pinfunction "XTAL2/MCLK_32") (pintype "input"))
      (node (ref "OSC1") (pin "3") (pinfunction "OUT_3") (pintype "bidirectional"))
    )
    (net (code "10") (name "ADC_NRESET") (class "Default")
      (node (ref "ADC") (pin "30") (pinfunction "~{RESET}_30") (pintype "input"))
      (node (ref "IC11") (pin "4") (pinfunction "P0_4") (pintype "bidirectional"))
      (node (ref "TP_ADC_NRESET") (pin "P$1") (pinfunction "P$1_P$1") (pintype "bidirectional"))
    )
    (net (code "11") (name "ADC_REF") (class "Default")
      (node (ref "ADC") (pin "43") (pinfunction "REF2+_43") (pintype "input"))
      (node (ref "ADC") (pin "6") (pinfunction "REF1+_6") (pintype "input"))
      (node (ref "C27") (pin "1") (pinfunction "1_1") (pintype "passive"))
      (node (ref "C28") (pin "1") (pinfunction "1_1") (pintype "passive"))
      (node (ref "SJ1") (pin "2") (pinfunction "2_2") (pintype "passive"))
    )
    (net (code "12") (name "AGND") (class "Default")
      (node (ref "ADC") (pin "10") (pinfunction "AVSS10_10") (pintype "power_in"))
      (node (ref "ADC") (pin "3") (pinfunction "AVSS1A_3") (pintype "power_in"))
      (node (ref "ADC") (pin "39") (pinfunction "AVSS39_39") (pintype "power_in"))
      (node (ref "ADC") (pin "40") (pinfunction "AVSS40_40") (pintype "power_in"))
      (node (ref "ADC") (pin "41") (pinfunction "AVSS41_41") (pintype "power_in"))
      (node (ref "ADC") (pin "42") (pinfunction "AVSS42_42") (pintype "power_in"))
      (node (ref "ADC") (pin "44") (pinfunction "REF2-_44") (pintype "input"))
      (node (ref "ADC") (pin "46") (pinfunction "AVSS1B_46") (pintype "passive"))
      (node (ref "ADC") (pin "47") (pinfunction "AIN3+_47") (pintype "input"))
      (node (ref "ADC") (pin "48") (pinfunction "AIN3-_48") (pintype "input"))
      (node (ref "ADC") (pin "49") (pinfunction "AIN2+_49") (pintype "input"))
      (node (ref "ADC") (pin "5") (pinfunction "REF1-_5") (pintype "input"))
      (node (ref "ADC") (pin "50") (pinfunction "AIN2-_50") (pintype "input"))
      (node (ref "ADC") (pin "51") (pinfunction "AVSS2B_51") (pintype "power_in"))
      (node (ref "ADC") (pin "54") (pinfunction "AVSS54_54") (pintype "power_in"))
      (node (ref "ADC") (pin "62") (pinfunction "AVSS2A_62") (pintype "power_in"))
      (node (ref "ADC") (pin "7") (pinfunction "AVSS7_7") (pintype "power_in"))
      (node (ref "ADC") (pin "8") (pinfunction "AVSS8_8") (pintype "power_in"))
      (node (ref "ADC") (pin "9") (pinfunction "AVSS9_9") (pintype "power_in"))
      (node (ref "C12") (pin "2") (pinfunction "2_2") (pintype "passive"))
      (node (ref "C13") (pin "2") (pinfunction "2_2") (pintype "passive"))
      (node (ref "C14") (pin "2") (pinfunction "2_2") (pintype "passive"))
      (node (ref "C15") (pin "2") (pinfunction "2_2") (pintype "passive"))
      (node (ref "C16") (pin "2") (pinfunction "2_2") (pintype "passive"))
      (node (ref "C17") (pin "2") (pinfunction "2_2") (pintype "passive"))
      (node (ref "C18") (pin "2") (pinfunction "2_2") (pintype "passive"))
      (node (ref "C19") (pin "2") (pinfunction "2_2") (pintype "passive"))
      (node (ref "C2") (pin "-") (pinfunction "-_-") (pintype "passive"))
      (node (ref "C22") (pin "2") (pinfunction "2_2") (pintype "passive"))
      (node (ref "C23") (pin "2") (pinfunction "2_2") (pintype "passive"))
      (node (ref "C24") (pin "2") (pinfunction "2_2") (pintype "passive"))
      (node (ref "C25") (pin "2") (pinfunction "2_2") (pintype "passive"))
      (node (ref "C27") (pin "2") (pinfunction "2_2") (pintype "passive"))
      (node (ref "C28") (pin "2") (pinfunction "2_2") (pintype "passive"))
      (node (ref "C29") (pin "1") (pinfunction "1_1") (pintype "passive"))
      (node (ref "C30") (pin "1") (pinfunction "1_1") (pintype "passive"))
      (node (ref "C31") (pin "1") (pinfunction "1_1") (pintype "passive"))
      (node (ref "C32") (pin "2") (pinfunction "2_2") (pintype "passive"))
      (node (ref "C36") (pin "2") (pinfunction "2_2") (pintype "passive"))
      (node (ref "C37") (pin "1") (pinfunction "1_1") (pintype "passive"))
      (node (ref "C38") (pin "2") (pinfunction "2_2") (pintype "passive"))
      (node (ref "C39") (pin "1") (pinfunction "1_1") (pintype "passive"))
      (node (ref "C40") (pin "2") (pinfunction "2_2") (pintype "passive"))
      (node (ref "C41") (pin "1") (pinfunction "1_1") (pintype "passive"))
      (node (ref "C42") (pin "1") (pinfunction "1_1") (pintype "passive"))
      (node (ref "C43") (pin "1") (pinfunction "1_1") (pintype "passive"))
      (node (ref "C44") (pin "1") (pinfunction "1_1") (pintype "passive"))
      (node (ref "C6") (pin "-") (pinfunction "-_-") (pintype "passive"))
      (node (ref "C7") (pin "-") (pinfunction "-_-") (pintype "passive"))
      (node (ref "C8") (pin "-") (pinfunction "-_-") (pintype "passive"))
      (node (ref "IC2") (pin "1") (pinfunction "GND_1") (pintype "input"))
      (node (ref "IC3") (pin "4") (pinfunction "GND_4") (pintype "bidirectional"))
      (node (ref "IC5") (pin "13") (pinfunction "-VCLAMP_13") (pintype "power_in"))
      (node (ref "IC5") (pin "14") (pinfunction "-VS_14") (pintype "power_in"))
      (node (ref "IC5") (pin "15") (pinfunction "-VS_15") (pintype "power_in"))
      (node (ref "IC5") (pin "16") (pinfunction "DGND_16") (pintype "power_in"))
      (node (ref "IC5") (pin "17") (pinfunction "EP_17") (pintype "power_in"))
      (node (ref "IC6") (pin "13") (pinfunction "-VCLAMP_13") (pintype "power_in"))
      (node (ref "IC6") (pin "14") (pinfunction "-VS_14") (pintype "power_in"))
      (node (ref "IC6") (pin "15") (pinfunction "-VS_15") (pintype "power_in"))
      (node (ref "IC6") (pin "16") (pinfunction "DGND_16") (pintype "power_in"))
      (node (ref "IC6") (pin "17") (pinfunction "EP_17") (pintype "power_in"))
      (node (ref "R2") (pin "2") (pinfunction "2_2") (pintype "passive"))
      (node (ref "R6") (pin "2") (pinfunction "2_2") (pintype "passive"))
      (node (ref "R7") (pin "1") (pinfunction "1_1") (pintype "passive"))
      (node (ref "TP_AGND1") (pin "P$1") (pinfunction "P$1_P$1") (pintype "bidirectional"))
      (node (ref "TP_AGND2") (pin "P$1") (pinfunction "P$1_P$1") (pintype "bidirectional"))
    )
    (net (code "13") (name "BITE_PS_+5V_CURRENT") (class "Default")
      (node (ref "CON_BACKPLANE") (pin "9") (pinfunction "9_9") (pintype "bidirectional"))
    )
    (net (code "14") (name "BITE_PS_5V_TS1") (class "Default")
      (node (ref "CON_BACKPLANE") (pin "11") (pinfunction "11_11") (pintype "bidirectional"))
    )
    (net (code "15") (name "BITE_PS_5V_TS2") (class "Default")
      (node (ref "CON_BACKPLANE") (pin "12") (pinfunction "12_12") (pintype "bidirectional"))
    )
    (net (code "16") (name "BITE_PS_12V_TS1") (class "Default")
      (node (ref "CON_BACKPLANE") (pin "13") (pinfunction "13_13") (pintype "bidirectional"))
    )
    (net (code "17") (name "BITE_PS_12V_TS2") (class "Default")
      (node (ref "CON_BACKPLANE") (pin "14") (pinfunction "14_14") (pintype "bidirectional"))
    )
    (net (code "18") (name "CON_EXT_CH1+") (class "Default")
      (node (ref "CON_EXT_CH1+") (pin "S") (pinfunction "S_S") (pintype "passive"))
      (node (ref "RELAY1") (pin "7") (pinfunction "7_7") (pintype "passive"))
    )
    (net (code "19") (name "CON_EXT_CH1-") (class "Default")
      (node (ref "CON_EXT_CH1-") (pin "S") (pinfunction "S_S") (pintype "passive"))
      (node (ref "RELAY1") (pin "2") (pinfunction "2_2") (pintype "passive"))
    )
    (net (code "20") (name "CON_EXT_CH2+") (class "Default")
      (node (ref "CON_EXT_CH2+") (pin "S") (pinfunction "S_S") (pintype "passive"))
      (node (ref "RELAY2") (pin "7") (pinfunction "7_7") (pintype "passive"))
    )
    (net (code "21") (name "CON_EXT_CH2-") (class "Default")
      (node (ref "CON_EXT_CH2-") (pin "S") (pinfunction "S_S") (pintype "passive"))
      (node (ref "RELAY2") (pin "2") (pinfunction "2_2") (pintype "passive"))
    )
    (net (code "22") (name "CON_INT_CH1+") (class "Default")
      (node (ref "CON_INT_CH1+") (pin "S") (pinfunction "SIG_S") (pintype "passive"))
      (node (ref "RELAY1") (pin "5") (pinfunction "5_5") (pintype "passive"))
    )
    (net (code "23") (name "CON_INT_CH1-") (class "Default")
      (node (ref "CON_INT_CH1-") (pin "S") (pinfunction "SIG_S") (pintype "passive"))
      (node (ref "RELAY1") (pin "4") (pinfunction "4_4") (pintype "passive"))
    )
    (net (code "24") (name "CON_INT_CH2+") (class "Default")
      (node (ref "CON_INT_CH2+") (pin "S") (pinfunction "SIG_S") (pintype "passive"))
      (node (ref "RELAY2") (pin "5") (pinfunction "5_5") (pintype "passive"))
    )
    (net (code "25") (name "CON_INT_CH2-") (class "Default")
      (node (ref "CON_INT_CH2-") (pin "S") (pinfunction "SIG_S") (pintype "passive"))
      (node (ref "RELAY2") (pin "4") (pinfunction "4_4") (pintype "passive"))
    )
    (net (code "26") (name "FDA1_IN_N") (class "Default")
      (node (ref "R18") (pin "2") (pinfunction "2_2") (pintype "passive"))
      (node (ref "RELAY1") (pin "3") (pinfunction "3_3") (pintype "passive"))
      (node (ref "TP_FDA1_IN_N") (pin "P$1") (pinfunction "P$1_P$1") (pintype "bidirectional"))
    )
    (net (code "27") (name "FDA1_IN_P") (class "Default")
      (node (ref "R17") (pin "2") (pinfunction "2_2") (pintype "passive"))
      (node (ref "RELAY1") (pin "6") (pinfunction "6_6") (pintype "passive"))
      (node (ref "TP_FDA1_IN_P") (pin "P$1") (pinfunction "P$1_P$1") (pintype "bidirectional"))
    )
    (net (code "28") (name "FDA2_IN_N") (class "Default")
      (node (ref "R22") (pin "2") (pinfunction "2_2") (pintype "passive"))
      (node (ref "RELAY2") (pin "3") (pinfunction "3_3") (pintype "passive"))
      (node (ref "TP_FDA2_IN_N") (pin "P$1") (pinfunction "P$1_P$1") (pintype "bidirectional"))
    )
    (net (code "29") (name "FDA2_IN_P") (class "Default")
      (node (ref "R21") (pin "2") (pinfunction "2_2") (pintype "passive"))
      (node (ref "RELAY2") (pin "6") (pinfunction "6_6") (pintype "passive"))
      (node (ref "TP_FDA2_IN_P") (pin "P$1") (pinfunction "P$1_P$1") (pintype "bidirectional"))
    )
    (net (code "30") (name "GND") (class "Default")
      (node (ref "ADC") (pin "31") (pinfunction "XTAL1_31") (pintype "input"))
      (node (ref "ADC") (pin "33") (pinfunction "DGND33_33") (pintype "power_in"))
      (node (ref "ADC") (pin "55") (pinfunction "DGND55_55") (pintype "power_in"))
      (node (ref "ADC") (pin "58") (pinfunction "CLK_SEL_58") (pintype "input"))
      (node (ref "C1") (pin "-") (pinfunction "-_-") (pintype "passive"))
      (node (ref "C10") (pin "2") (pinfunction "2_2") (pintype "passive"))
      (node (ref "C11") (pin "2") (pinfunction "2_2") (pintype "passive"))
      (node (ref "C20") (pin "2") (pinfunction "2_2") (pintype "passive"))
      (node (ref "C21") (pin "2") (pinfunction "2_2") (pintype "passive"))
      (node (ref "C26") (pin "1") (pinfunction "1_1") (pintype "passive"))
      (node (ref "C4") (pin "-") (pinfunction "-_-") (pintype "passive"))
      (node (ref "C5") (pin "-") (pinfunction "-_-") (pintype "passive"))
      (node (ref "C65") (pin "2") (pinfunction "2_2") (pintype "passive"))
      (node (ref "C66") (pin "2") (pinfunction "2_2") (pintype "passive"))
      (node (ref "C9") (pin "2") (pinfunction "2_2") (pintype "passive"))
      (node (ref "CON_BACKPLANE") (pin "10") (pinfunction "10_10") (pintype "bidirectional"))
      (node (ref "CON_BACKPLANE") (pin "15") (pinfunction "15_15") (pintype "bidirectional"))
      (node (ref "CON_BACKPLANE") (pin "25") (pinfunction "25_25") (pintype "bidirectional"))
      (node (ref "CON_BACKPLANE") (pin "26") (pinfunction "26_26") (pintype "bidirectional"))
      (node (ref "CON_BACKPLANE") (pin "27") (pinfunction "27_27") (pintype "bidirectional"))
      (node (ref "CON_BACKPLANE") (pin "28") (pinfunction "28_28") (pintype "bidirectional"))
      (node (ref "CON_BACKPLANE") (pin "29") (pinfunction "29_29") (pintype "bidirectional"))
      (node (ref "CON_BACKPLANE") (pin "3") (pinfunction "3_3") (pintype "bidirectional"))
      (node (ref "CON_BACKPLANE") (pin "30") (pinfunction "30_30") (pintype "bidirectional"))
      (node (ref "CON_BACKPLANE") (pin "31") (pinfunction "31_31") (pintype "bidirectional"))
      (node (ref "CON_BACKPLANE") (pin "32") (pinfunction "32_32") (pintype "bidirectional"))
      (node (ref "CON_BACKPLANE") (pin "4") (pinfunction "4_4") (pintype "bidirectional"))
      (node (ref "CON_BACKPLANE") (pin "7") (pinfunction "7_7") (pintype "bidirectional"))
      (node (ref "CON_BACKPLANE") (pin "8") (pinfunction "8_8") (pintype "bidirectional"))
      (node (ref "IC1") (pin "1") (pinfunction "GND_1") (pintype "input"))
      (node (ref "IC11") (pin "1") (pinfunction "A0_1") (pintype "bidirectional"))
      (node (ref "IC11") (pin "2") (pinfunction "A1_2") (pintype "bidirectional"))
      (node (ref "IC11") (pin "3") (pinfunction "A2_3") (pintype "bidirectional"))
      (node (ref "IC11") (pin "8") (pinfunction "GND_8") (pintype "power_in"))
      (node (ref "OSC1") (pin "2") (pinfunction "GND_2") (pintype "bidirectional"))
      (node (ref "R1") (pin "2") (pinfunction "2_2") (pintype "passive"))
      (node (ref "R4") (pin "1") (pinfunction "1_1") (pintype "passive"))
      (node (ref "R5") (pin "1") (pinfunction "1_1") (pintype "passive"))
      (node (ref "R7") (pin "2") (pinfunction "2_2") (pintype "passive"))
      (node (ref "RD") (pin "12") (pinfunction "PGND_12") (pintype "power_in"))
      (node (ref "RD") (pin "18") (pinfunction "PGND_18") (pintype "power_in"))
      (node (ref "RD") (pin "21") (pinfunction "GND_21") (pintype "power_in"))
      (node (ref "RD") (pin "9") (pinfunction "GND_9") (pintype "power_in"))
      (node (ref "TP_GND1") (pin "P$1") (pinfunction "P$1_P$1") (pintype "bidirectional"))
      (node (ref "TP_GND2") (pin "P$1") (pinfunction "P$1_P$1") (pintype "bidirectional"))
    )
    (net (code "31") (name "I2C_NINT") (class "Default")
      (node (ref "CON_BACKPLANE") (pin "22") (pinfunction "22_22") (pintype "bidirectional"))
      (node (ref "IC11") (pin "13") (pinfunction "~{INT}_13") (pintype "bidirectional"))
      (node (ref "TP_I2C_NINT") (pin "P$1") (pinfunction "P$1_P$1") (pintype "bidirectional"))
    )
    (net (code "32") (name "I2C_SCL") (class "Default")
      (node (ref "CON_BACKPLANE") (pin "24") (pinfunction "24_24") (pintype "bidirectional"))
      (node (ref "IC11") (pin "14") (pinfunction "SCL_14") (pintype "bidirectional"))
      (node (ref "TP_I2C_SCL") (pin "P$1") (pinfunction "P$1_P$1") (pintype "bidirectional"))
    )
    (net (code "33") (name "I2C_SDA") (class "Default")
      (node (ref "CON_BACKPLANE") (pin "23") (pinfunction "23_23") (pintype "bidirectional"))
      (node (ref "IC11") (pin "15") (pinfunction "SDA_15") (pintype "bidirectional"))
      (node (ref "TP_I2C_SDA") (pin "P$1") (pinfunction "P$1_P$1") (pintype "bidirectional"))
    )
    (net (code "34") (name "Net-(ADC-DIN)") (class "Default")
      (node (ref "ADC") (pin "21") (pinfunction "DIN_21") (pintype "power_in"))
      (node (ref "R5") (pin "2") (pinfunction "2_2") (pintype "passive"))
    )
    (net (code "35") (name "Net-(ADC-DNC{slash}DGND)") (class "Default")
      (node (ref "ADC") (pin "20") (pinfunction "DNC/DGND_20") (pintype "power_in"))
      (node (ref "R4") (pin "2") (pinfunction "2_2") (pintype "passive"))
    )
    (net (code "36") (name "Net-(ADC-DREGCAP)") (class "Default")
      (node (ref "ADC") (pin "34") (pinfunction "DREGCAP_34") (pintype "output"))
      (node (ref "C20") (pin "1") (pinfunction "1_1") (pintype "passive"))
      (node (ref "C21") (pin "1") (pinfunction "1_1") (pintype "passive"))
    )
    (net (code "37") (name "Net-(ADC-REGCAPA)") (class "Default")
      (node (ref "ADC") (pin "61") (pinfunction "REGCAPA_61") (pintype "output"))
      (node (ref "C24") (pin "1") (pinfunction "1_1") (pintype "passive"))
      (node (ref "C25") (pin "1") (pinfunction "1_1") (pintype "passive"))
    )
    (net (code "38") (name "Net-(ADC-REGCAPB)") (class "Default")
      (node (ref "ADC") (pin "52") (pinfunction "REGCAPB_52") (pintype "output"))
      (node (ref "C22") (pin "1") (pinfunction "1_1") (pintype "passive"))
      (node (ref "C23") (pin "1") (pinfunction "1_1") (pintype "passive"))
    )
    (net (code "39") (name "Net-(ADC-~{START})") (class "Default")
      (node (ref "ADC") (pin "37") (pinfunction "~{START}_37") (pintype "input"))
      (node (ref "R3") (pin "2") (pinfunction "2_2") (pintype "passive"))
    )
    (net (code "40") (name "Net-(ADC-~{SYNC_IN})") (class "Default")
      (node (ref "ADC") (pin "36") (pinfunction "~{SYNC_IN}_36") (pintype "input"))
      (node (ref "ADC") (pin "38") (pinfunction "~{SYNC_OUT}_38") (pintype "output"))
    )
    (net (code "41") (name "Net-(C32-Pad1)") (class "Default")
      (node (ref "C32") (pin "1") (pinfunction "1_1") (pintype "passive"))
      (node (ref "R6") (pin "1") (pinfunction "1_1") (pintype "passive"))
      (node (ref "RELAY3") (pin "2") (pinfunction "2_2") (pintype "passive"))
      (node (ref "RELAY3") (pin "7") (pinfunction "7_7") (pintype "passive"))
    )
    (net (code "42") (name "Net-(IC2-IN)") (class "Default")
      (node (ref "C7") (pin "+") (pinfunction "+_+") (pintype "passive"))
      (node (ref "IC2") (pin "3") (pinfunction "IN_3") (pintype "input"))
      (node (ref "L1") (pin "2") (pinfunction "2_2") (pintype "passive"))
    )
    (net (code "43") (name "Net-(IC5-+FB)") (class "Default")
      (node (ref "C54") (pin "1") (pinfunction "1_1") (pintype "passive"))
      (node (ref "IC5") (pin "4") (pinfunction "+FB_4") (pintype "input"))
      (node (ref "R16") (pin "1") (pinfunction "1_1") (pintype "passive"))
    )
    (net (code "44") (name "Net-(IC5-+IN)") (class "Default")
      (node (ref "C53") (pin "1") (pinfunction "1_1") (pintype "passive"))
      (node (ref "IC5") (pin "2") (pinfunction "+IN_2") (pintype "input"))
      (node (ref "R15") (pin "2") (pinfunction "2_2") (pintype "passive"))
      (node (ref "R17") (pin "1") (pinfunction "1_1") (pintype "passive"))
    )
    (net (code "45") (name "Net-(IC5-+OUT)") (class "Default")
      (node (ref "IC5") (pin "10") (pinfunction "+OUT_10") (pintype "output"))
      (node (ref "R10") (pin "2") (pinfunction "2_2") (pintype "passive"))
    )
    (net (code "46") (name "Net-(IC5--FB)") (class "Default")
      (node (ref "C53") (pin "2") (pinfunction "2_2") (pintype "passive"))
      (node (ref "IC5") (pin "1") (pinfunction "-FB_1") (pintype "input"))
      (node (ref "R15") (pin "1") (pinfunction "1_1") (pintype "passive"))
    )
    (net (code "47") (name "Net-(IC5--IN)") (class "Default")
      (node (ref "C54") (pin "2") (pinfunction "2_2") (pintype "passive"))
      (node (ref "IC5") (pin "3") (pinfunction "-IN_3") (pintype "input"))
      (node (ref "R16") (pin "2") (pinfunction "2_2") (pintype "passive"))
      (node (ref "R18") (pin "1") (pinfunction "1_1") (pintype "passive"))
    )
    (net (code "48") (name "Net-(IC5--OUT)") (class "Default")
      (node (ref "IC5") (pin "11") (pinfunction "-OUT_11") (pintype "output"))
      (node (ref "R11") (pin "2") (pinfunction "2_2") (pintype "passive"))
    )
    (net (code "49") (name "Net-(IC6-+FB)") (class "Default")
      (node (ref "C56") (pin "1") (pinfunction "1_1") (pintype "passive"))
      (node (ref "IC6") (pin "4") (pinfunction "+FB_4") (pintype "input"))
      (node (ref "R20") (pin "1") (pinfunction "1_1") (pintype "passive"))
    )
    (net (code "50") (name "Net-(IC6-+IN)") (class "Default")
      (node (ref "C55") (pin "1") (pinfunction "1_1") (pintype "passive"))
      (node (ref "IC6") (pin "2") (pinfunction "+IN_2") (pintype "input"))
      (node (ref "R19") (pin "2") (pinfunction "2_2") (pintype "passive"))
      (node (ref "R21") (pin "1") (pinfunction "1_1") (pintype "passive"))
    )
    (net (code "51") (name "Net-(IC6-+OUT)") (class "Default")
      (node (ref "IC6") (pin "10") (pinfunction "+OUT_10") (pintype "output"))
      (node (ref "R12") (pin "2") (pinfunction "2_2") (pintype "passive"))
    )
    (net (code "52") (name "Net-(IC6--FB)") (class "Default")
      (node (ref "C55") (pin "2") (pinfunction "2_2") (pintype "passive"))
      (node (ref "IC6") (pin "1") (pinfunction "-FB_1") (pintype "input"))
      (node (ref "R19") (pin "1") (pinfunction "1_1") (pintype "passive"))
    )
    (net (code "53") (name "Net-(IC6--IN)") (class "Default")
      (node (ref "C56") (pin "2") (pinfunction "2_2") (pintype "passive"))
      (node (ref "IC6") (pin "3") (pinfunction "-IN_3") (pintype "input"))
      (node (ref "R20") (pin "2") (pinfunction "2_2") (pintype "passive"))
      (node (ref "R22") (pin "1") (pinfunction "1_1") (pintype "passive"))
    )
    (net (code "54") (name "Net-(IC6--OUT)") (class "Default")
      (node (ref "IC6") (pin "11") (pinfunction "-OUT_11") (pintype "output"))
      (node (ref "R13") (pin "2") (pinfunction "2_2") (pintype "passive"))
    )
    (net (code "55") (name "Net-(LED_+3.3V-PadC)") (class "Default")
      (node (ref "LED_+3.3V") (pin "C") (pinfunction "C_C") (pintype "passive"))
      (node (ref "R1") (pin "1") (pinfunction "1_1") (pintype "passive"))
    )
    (net (code "56") (name "Net-(LED_+5V_ANALOG-PadC)") (class "Default")
      (node (ref "LED_+5V_ANALOG") (pin "C") (pinfunction "C_C") (pintype "passive"))
      (node (ref "R2") (pin "1") (pinfunction "1_1") (pintype "passive"))
    )
    (net (code "57") (name "RD_NRESET") (class "Default")
      (node (ref "IC11") (pin "7") (pinfunction "P3_7") (pintype "bidirectional"))
      (node (ref "RD") (pin "3") (pinfunction "~{RESET}_3") (pintype "input"))
      (node (ref "TP_RD_NRESET") (pin "P$1") (pinfunction "P$1_P$1") (pintype "bidirectional"))
    )
    (net (code "58") (name "RD_OUT1") (class "Default")
      (node (ref "R27") (pin "1") (pinfunction "1_1") (pintype "passive"))
      (node (ref "RD") (pin "20") (pinfunction "OUT1_20") (pintype "output"))
      (node (ref "RELAY1") (pin "1") (pinfunction "1_1") (pintype "passive"))
    )
    (net (code "59") (name "RD_OUT2") (class "Default")
      (node (ref "R28") (pin "1") (pinfunction "1_1") (pintype "passive"))
      (node (ref "RD") (pin "19") (pinfunction "OUT2_19") (pintype "output"))
      (node (ref "RELAY1") (pin "8") (pinfunction "8_8") (pintype "passive"))
    )
    (net (code "60") (name "RD_OUT3") (class "Default")
      (node (ref "R29") (pin "1") (pinfunction "1_1") (pintype "passive"))
      (node (ref "RD") (pin "17") (pinfunction "OUT3_17") (pintype "output"))
      (node (ref "RELAY2") (pin "1") (pinfunction "1_1") (pintype "passive"))
    )
    (net (code "61") (name "RD_OUT4") (class "Default")
      (node (ref "R30") (pin "1") (pinfunction "1_1") (pintype "passive"))
      (node (ref "RD") (pin "16") (pinfunction "OUT4_16") (pintype "output"))
      (node (ref "RELAY2") (pin "8") (pinfunction "8_8") (pintype "passive"))
    )
    (net (code "62") (name "RD_OUT5") (class "Default")
      (node (ref "R31") (pin "1") (pinfunction "1_1") (pintype "passive"))
      (node (ref "RD") (pin "14") (pinfunction "OUT5_14") (pintype "output"))
      (node (ref "RELAY3") (pin "1") (pinfunction "1_1") (pintype "passive"))
    )
    (net (code "63") (name "RD_OUT6") (class "Default")
      (node (ref "R32") (pin "1") (pinfunction "1_1") (pintype "passive"))
      (node (ref "RD") (pin "13") (pinfunction "OUT6_13") (pintype "output"))
      (node (ref "RELAY3") (pin "8") (pinfunction "8_8") (pintype "passive"))
    )
    (net (code "64") (name "SHIELD") (class "Default")
      (node (ref "CON_EXT_CH1+") (pin "G1") (pinfunction "G_G1") (pintype "passive"))
      (node (ref "CON_EXT_CH1+") (pin "G2") (pinfunction "G_G2") (pintype "passive"))
      (node (ref "CON_EXT_CH1+") (pin "G3") (pinfunction "G_G3") (pintype "passive"))
      (node (ref "CON_EXT_CH1+") (pin "G4") (pinfunction "G_G4") (pintype "passive"))
      (node (ref "CON_EXT_CH1-") (pin "G1") (pinfunction "G_G1") (pintype "passive"))
      (node (ref "CON_EXT_CH1-") (pin "G2") (pinfunction "G_G2") (pintype "passive"))
      (node (ref "CON_EXT_CH1-") (pin "G3") (pinfunction "G_G3") (pintype "passive"))
      (node (ref "CON_EXT_CH1-") (pin "G4") (pinfunction "G_G4") (pintype "passive"))
      (node (ref "CON_EXT_CH2+") (pin "G1") (pinfunction "G_G1") (pintype "passive"))
      (node (ref "CON_EXT_CH2+") (pin "G2") (pinfunction "G_G2") (pintype "passive"))
      (node (ref "CON_EXT_CH2+") (pin "G3") (pinfunction "G_G3") (pintype "passive"))
      (node (ref "CON_EXT_CH2+") (pin "G4") (pinfunction "G_G4") (pintype "passive"))
      (node (ref "CON_EXT_CH2-") (pin "G1") (pinfunction "G_G1") (pintype "passive"))
      (node (ref "CON_EXT_CH2-") (pin "G2") (pinfunction "G_G2") (pintype "passive"))
      (node (ref "CON_EXT_CH2-") (pin "G3") (pinfunction "G_G3") (pintype "passive"))
      (node (ref "CON_EXT_CH2-") (pin "G4") (pinfunction "G_G4") (pintype "passive"))
      (node (ref "CON_INT_CH1+") (pin "G1") (pinfunction "GND_G1") (pintype "passive"))
      (node (ref "CON_INT_CH1+") (pin "G2") (pinfunction "GND_G2") (pintype "passive"))
      (node (ref "CON_INT_CH1-") (pin "G1") (pinfunction "GND_G1") (pintype "passive"))
      (node (ref "CON_INT_CH1-") (pin "G2") (pinfunction "GND_G2") (pintype "passive"))
      (node (ref "CON_INT_CH2+") (pin "G1") (pinfunction "GND_G1") (pintype "passive"))
      (node (ref "CON_INT_CH2+") (pin "G2") (pinfunction "GND_G2") (pintype "passive"))
      (node (ref "CON_INT_CH2-") (pin "G1") (pinfunction "GND_G1") (pintype "passive"))
      (node (ref "CON_INT_CH2-") (pin "G2") (pinfunction "GND_G2") (pintype "passive"))
      (node (ref "RELAY3") (pin "3") (pinfunction "3_3") (pintype "passive"))
      (node (ref "RELAY3") (pin "6") (pinfunction "6_6") (pintype "passive"))
      (node (ref "TP_SHIELD1") (pin "P$1") (pinfunction "P$1_P$1") (pintype "bidirectional"))
    )
    (net (code "65") (name "SPI_CONFIG_ADC_NCS") (class "Default")
      (node (ref "ADC") (pin "16") (pinfunction "ST0/~{CS}_16") (pintype "input"))
      (node (ref "IC11") (pin "5") (pinfunction "P1_5") (pintype "bidirectional"))
      (node (ref "TP_SPI_CONFIG_ADC_NCS") (pin "P$1") (pinfunction "P$1_P$1") (pintype "bidirectional"))
    )
    (net (code "66") (name "SPI_CONFIG_CLK") (class "Default")
      (node (ref "ADC") (pin "17") (pinfunction "SCLK_17") (pintype "input"))
      (node (ref "CON_BACKPLANE") (pin "21") (pinfunction "21_21") (pintype "bidirectional"))
      (node (ref "RD") (pin "6") (pinfunction "SCLK_6") (pintype "input"))
      (node (ref "TP_SPI_CONFIG_CLK") (pin "P$1") (pinfunction "P$1_P$1") (pintype "bidirectional"))
    )
    (net (code "67") (name "SPI_CONFIG_MISO") (class "Default")
      (node (ref "ADC") (pin "19") (pinfunction "DEC0/SDO_19") (pintype "output"))
      (node (ref "CON_BACKPLANE") (pin "19") (pinfunction "19_19") (pintype "bidirectional"))
      (node (ref "RD") (pin "7") (pinfunction "DOUT_7") (pintype "output"))
      (node (ref "TP_SPI_CONFIG_MISO") (pin "P$1") (pinfunction "P$1_P$1") (pintype "bidirectional"))
    )
    (net (code "68") (name "SPI_CONFIG_MOSI") (class "Default")
      (node (ref "ADC") (pin "18") (pinfunction "DEC1/SDI_18") (pintype "input"))
      (node (ref "CON_BACKPLANE") (pin "20") (pinfunction "20_20") (pintype "bidirectional"))
      (node (ref "RD") (pin "5") (pinfunction "DIN_5") (pintype "input"))
      (node (ref "TP_SPI_CONFIG_MOSI") (pin "P$1") (pinfunction "P$1_P$1") (pintype "bidirectional"))
    )
    (net (code "69") (name "SPI_CONFIG_RD_NCS") (class "Default")
      (node (ref "IC11") (pin "6") (pinfunction "P2_6") (pintype "bidirectional"))
      (node (ref "RD") (pin "4") (pinfunction "~{CS}_4") (pintype "input"))
      (node (ref "TP_SPI_CONFIG_RD_NCS") (pin "P$1") (pinfunction "P$1_P$1") (pintype "bidirectional"))
    )
    (net (code "70") (name "SPI_DATA_CLK") (class "Default")
      (node (ref "ADC") (pin "28") (pinfunction "DCLK_28") (pintype "output"))
      (node (ref "CON_BACKPLANE") (pin "17") (pinfunction "17_17") (pintype "bidirectional"))
      (node (ref "TP_SPI_DATA_CLK") (pin "P$1") (pinfunction "P$1_P$1") (pintype "bidirectional"))
    )
    (net (code "71") (name "SPI_DATA_MOSI") (class "Default")
      (node (ref "ADC") (pin "27") (pinfunction "DOUT0_27") (pintype "output"))
      (node (ref "CON_BACKPLANE") (pin "18") (pinfunction "18_18") (pintype "bidirectional"))
      (node (ref "TP_SPI_DATA_MOSI") (pin "P$1") (pinfunction "P$1_P$1") (pintype "bidirectional"))
    )
    (net (code "72") (name "SPI_DATA_NCS") (class "Default")
      (node (ref "ADC") (pin "29") (pinfunction "~{DRDY}_29") (pintype "output"))
      (node (ref "CON_BACKPLANE") (pin "16") (pinfunction "16_16") (pintype "bidirectional"))
      (node (ref "TP_SPI_DATA_NCS") (pin "P$1") (pinfunction "P$1_P$1") (pintype "bidirectional"))
    )
    (net (code "73") (name "VCM") (class "Default")
      (node (ref "C40") (pin "1") (pinfunction "1_1") (pintype "passive"))
      (node (ref "IC5") (pin "9") (pinfunction "VOCM_9") (pintype "passive"))
      (node (ref "IC6") (pin "9") (pinfunction "VOCM_9") (pintype "passive"))
      (node (ref "R14") (pin "2") (pinfunction "2_2") (pintype "passive"))
      (node (ref "TP_VCM") (pin "P$1") (pinfunction "P$1_P$1") (pintype "bidirectional"))
    )
    (net (code "74") (name "VCM_ADC") (class "Default")
      (node (ref "ADC") (pin "59") (pinfunction "VCM_59") (pintype "output"))
      (node (ref "R14") (pin "1") (pinfunction "1_1") (pintype "passive"))
      (node (ref "TP_VCM_ADC") (pin "P$1") (pinfunction "P$1_P$1") (pintype "bidirectional"))
    )
    (net (code "75") (name "VREF_5V") (class "Default")
      (node (ref "C31") (pin "2") (pinfunction "2_2") (pintype "passive"))
      (node (ref "IC3") (pin "6") (pinfunction "VOUT_6") (pintype "bidirectional"))
      (node (ref "SJ1") (pin "1") (pinfunction "1_1") (pintype "passive"))
      (node (ref "TP_VREF_5V") (pin "P$1") (pinfunction "P$1_P$1") (pintype "bidirectional"))
    )
    (net (code "76") (name "unconnected-(ADC-DNC22-Pad22)") (class "Default")
      (node (ref "ADC") (pin "22") (pinfunction "DNC22_22") (pintype "no_connect"))
    )
    (net (code "77") (name "unconnected-(ADC-DNC23-Pad23)") (class "Default")
      (node (ref "ADC") (pin "23") (pinfunction "DNC23_23") (pintype "no_connect"))
    )
    (net (code "78") (name "unconnected-(ADC-DOUT1-Pad26)") (class "Default")
      (node (ref "ADC") (pin "26") (pinfunction "DOUT1_26") (pintype "output"))
    )
    (net (code "79") (name "unconnected-(ADC-DOUT2-Pad25)") (class "Default")
      (node (ref "ADC") (pin "25") (pinfunction "DOUT2_25") (pintype "output"))
    )
    (net (code "80") (name "unconnected-(ADC-DOUT3-Pad24)") (class "Default")
      (node (ref "ADC") (pin "24") (pinfunction "DOUT3_24") (pintype "output"))
    )
    (net (code "81") (name "unconnected-(ADC-FILTER{slash}GPIO4-Pad11)") (class "Default")
      (node (ref "ADC") (pin "11") (pinfunction "FILTER/GPIO4_11") (pintype "bidirectional"))
    )
    (net (code "82") (name "unconnected-(ADC-MODE0{slash}GPIO0-Pad12)") (class "Default")
      (node (ref "ADC") (pin "12") (pinfunction "MODE0/GPIO0_12") (pintype "bidirectional"))
    )
    (net (code "83") (name "unconnected-(ADC-MODE1{slash}GPIO1-Pad13)") (class "Default")
      (node (ref "ADC") (pin "13") (pinfunction "MODE1/GPIO1_13") (pintype "bidirectional"))
    )
    (net (code "84") (name "unconnected-(ADC-MODE2{slash}GPIO2-Pad14)") (class "Default")
      (node (ref "ADC") (pin "14") (pinfunction "MODE2/GPIO2_14") (pintype "bidirectional"))
    )
    (net (code "85") (name "unconnected-(ADC-MODE3{slash}GPIO3-Pad15)") (class "Default")
      (node (ref "ADC") (pin "15") (pinfunction "MODE3/GPIO3_15") (pintype "bidirectional"))
    )
    (net (code "86") (name "unconnected-(CON_BACKPLANE-Pad6)") (class "Default")
      (node (ref "CON_BACKPLANE") (pin "6") (pinfunction "6_6") (pintype "bidirectional"))
    )
    (net (code "87") (name "unconnected-(IC3-TRIM-Pad5)") (class "Default")
      (node (ref "IC3") (pin "5") (pinfunction "TRIM_5") (pintype "bidirectional"))
    )
    (net (code "88") (name "unconnected-(IC11-P4-Pad9)") (class "Default")
      (node (ref "IC11") (pin "9") (pinfunction "P4_9") (pintype "bidirectional"))
    )
    (net (code "89") (name "unconnected-(IC11-P5-Pad10)") (class "Default")
      (node (ref "IC11") (pin "10") (pinfunction "P5_10") (pintype "bidirectional"))
    )
    (net (code "90") (name "unconnected-(IC11-P6-Pad11)") (class "Default")
      (node (ref "IC11") (pin "11") (pinfunction "P6_11") (pintype "bidirectional"))
    )
    (net (code "91") (name "unconnected-(IC11-P7-Pad12)") (class "Default")
      (node (ref "IC11") (pin "12") (pinfunction "P7_12") (pintype "bidirectional"))
    )
    (net (code "92") (name "unconnected-(RD-OUT7-Pad11)") (class "Default")
      (node (ref "RD") (pin "11") (pinfunction "OUT7_11") (pintype "output"))
    )
    (net (code "93") (name "unconnected-(RD-OUT8-Pad10)") (class "Default")
      (node (ref "RD") (pin "10") (pinfunction "OUT8_10") (pintype "output"))
    )
    (net (code "94") (name "unconnected-(RELAY3-Pad4)") (class "Default")
      (node (ref "RELAY3") (pin "4") (pinfunction "4_4") (pintype "passive"))
    )
    (net (code "95") (name "unconnected-(RELAY3-Pad5)") (class "Default")
      (node (ref "RELAY3") (pin "5") (pinfunction "5_5") (pintype "passive"))
    )
  )
)
